# Hutschienenmoped_XL_12V.net
KiCad netlist of a schematic drawn in EAGLE
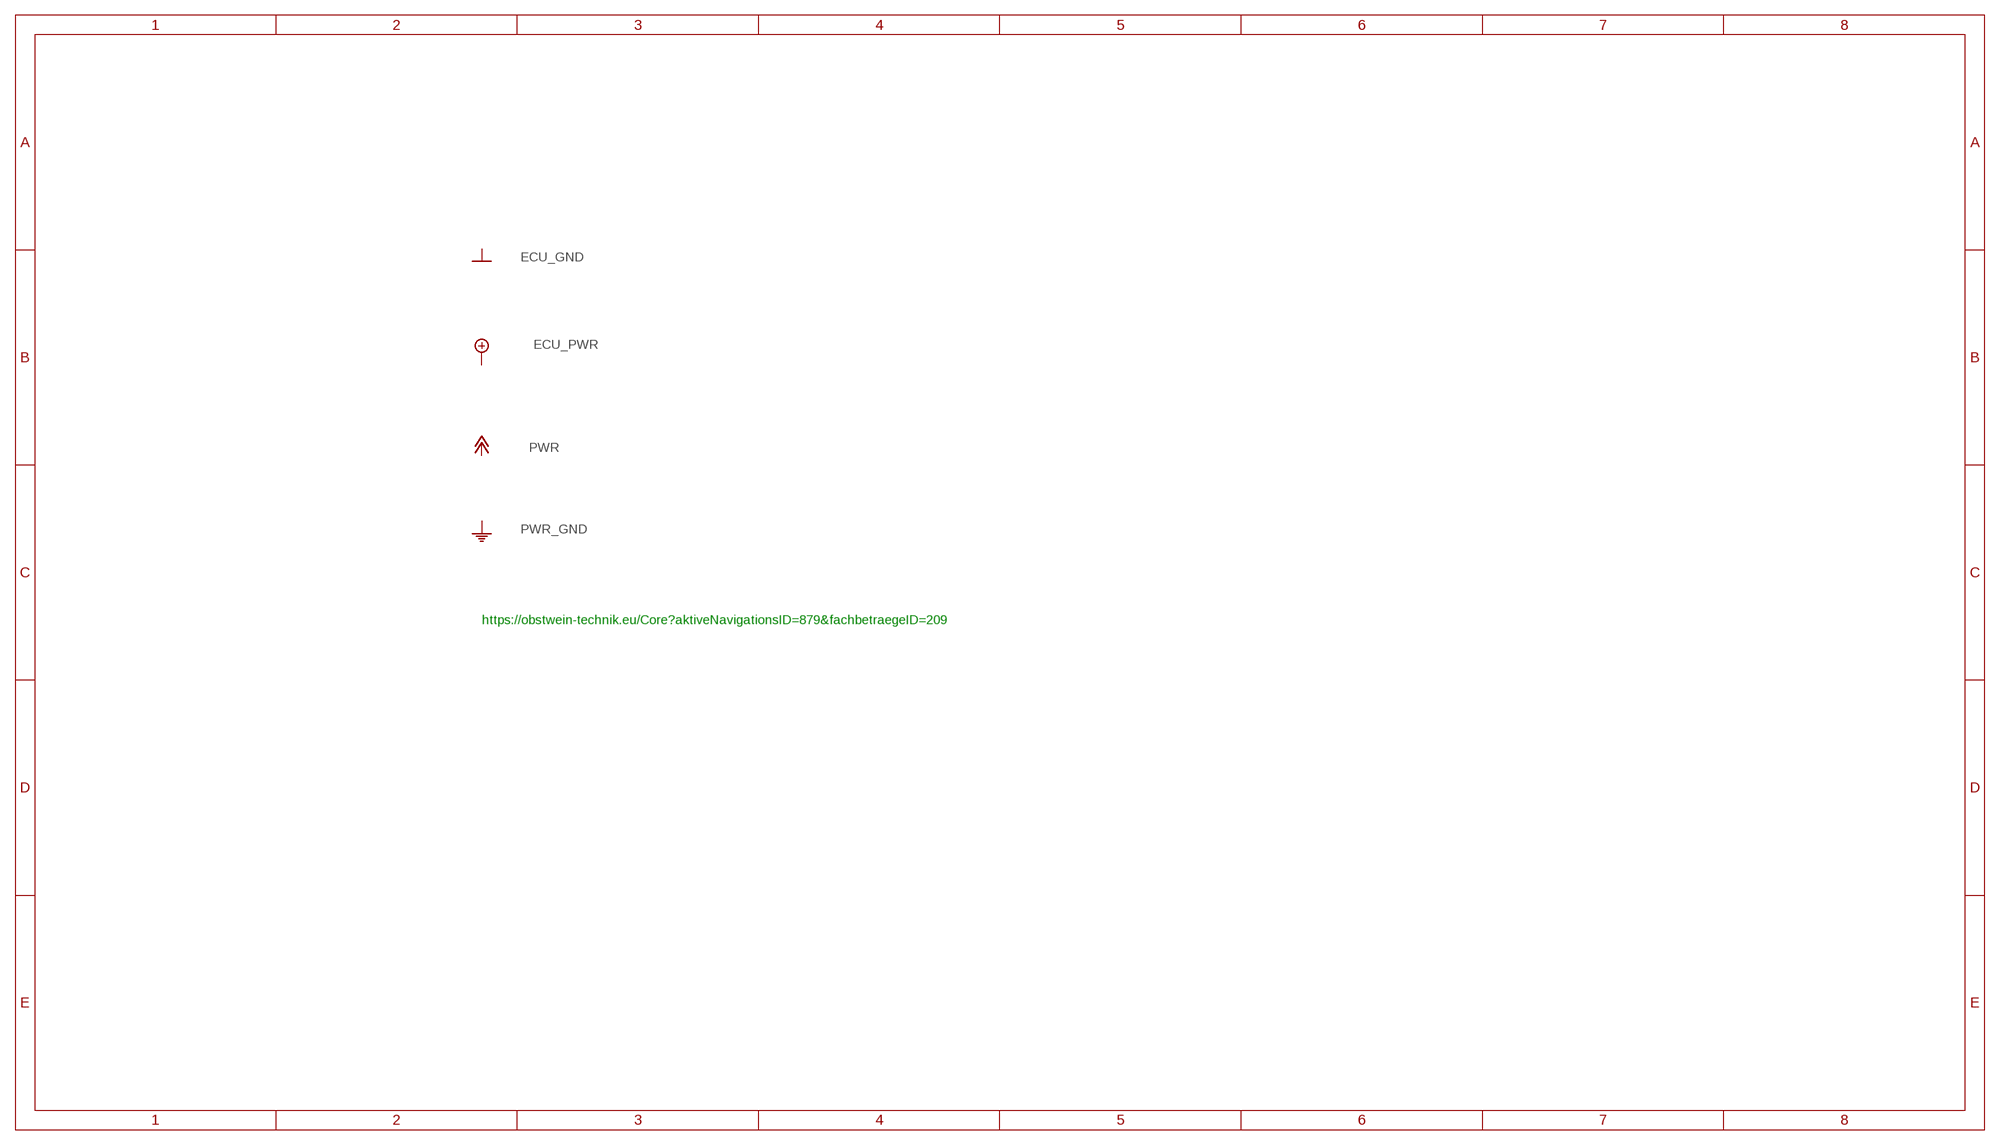
[diagram p0: schematic, sheet 1]
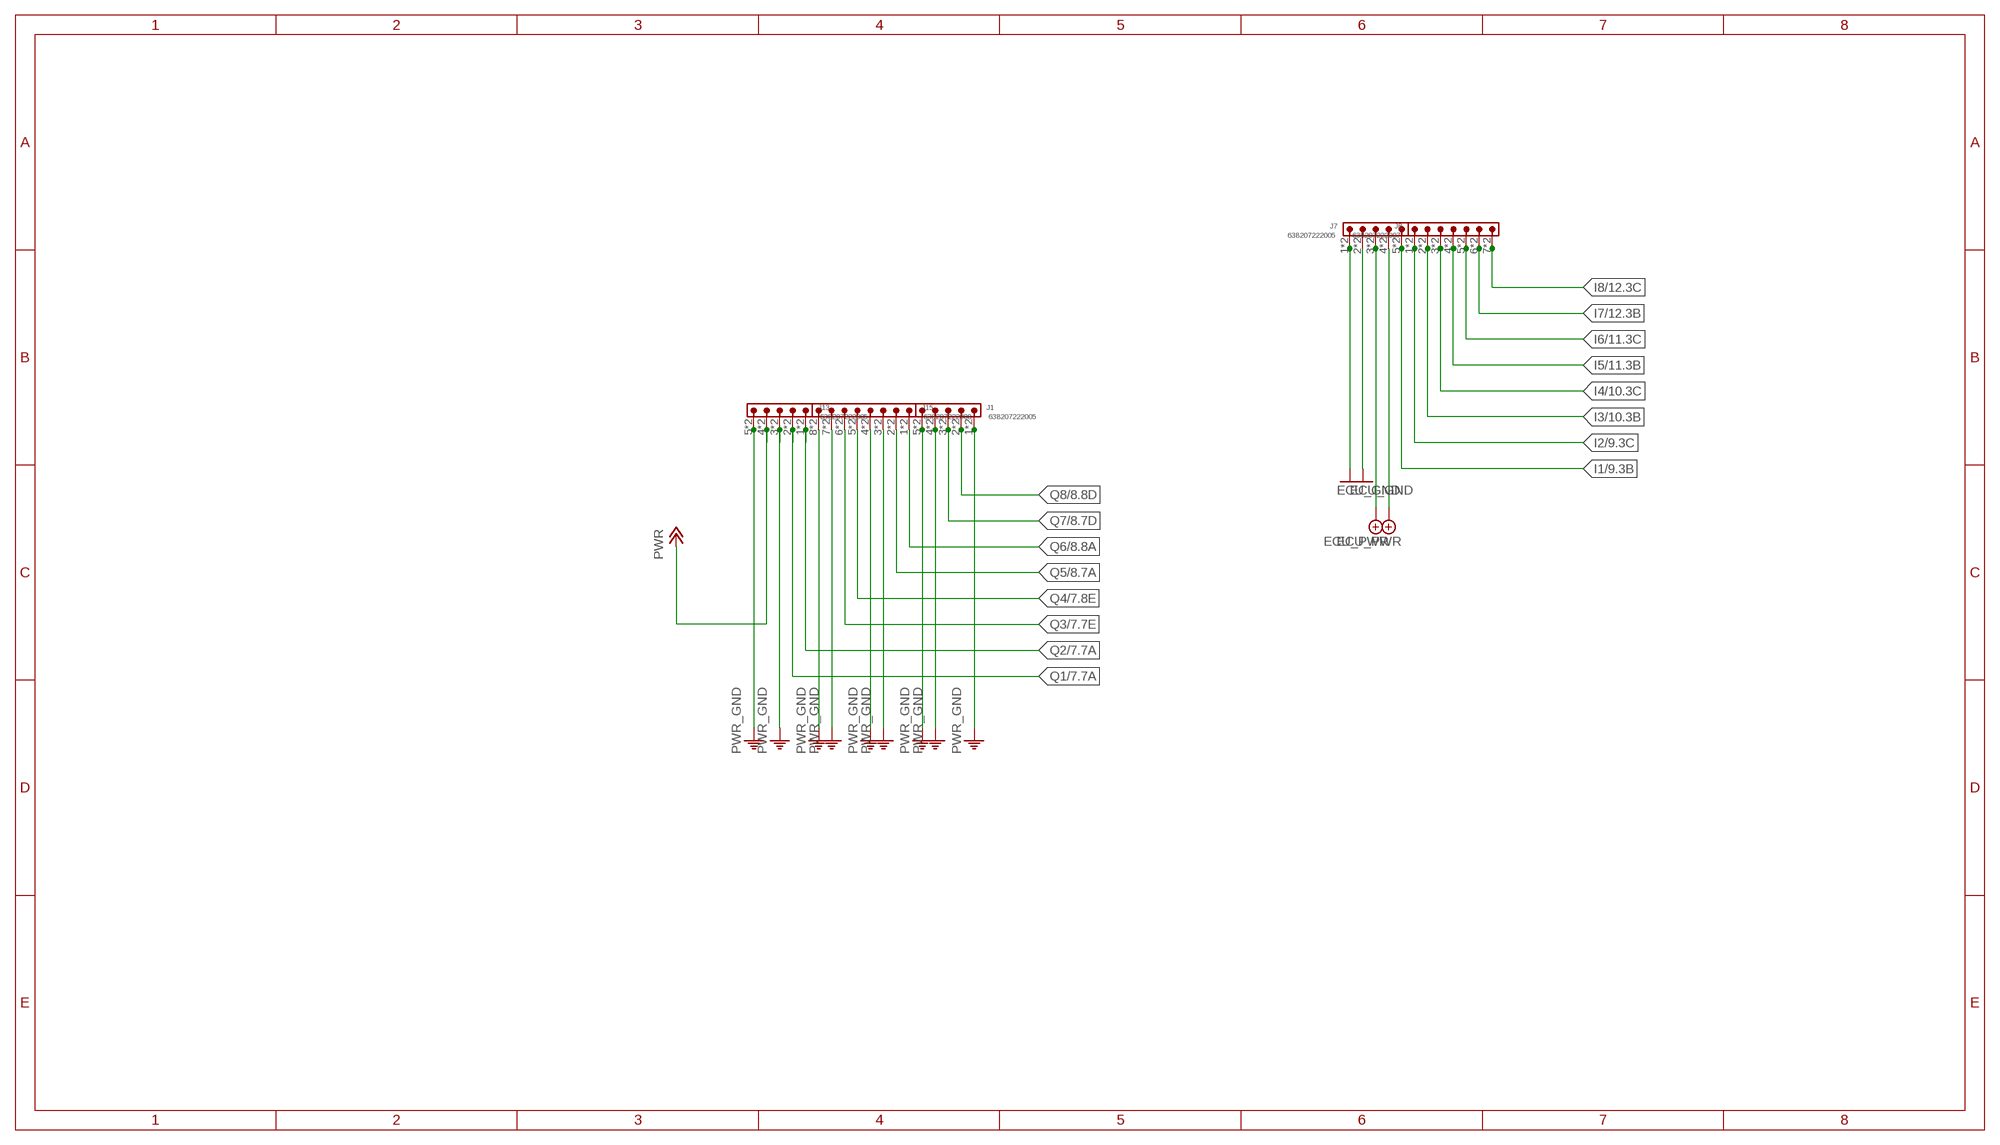
[diagram p1: schematic, sheet 2]
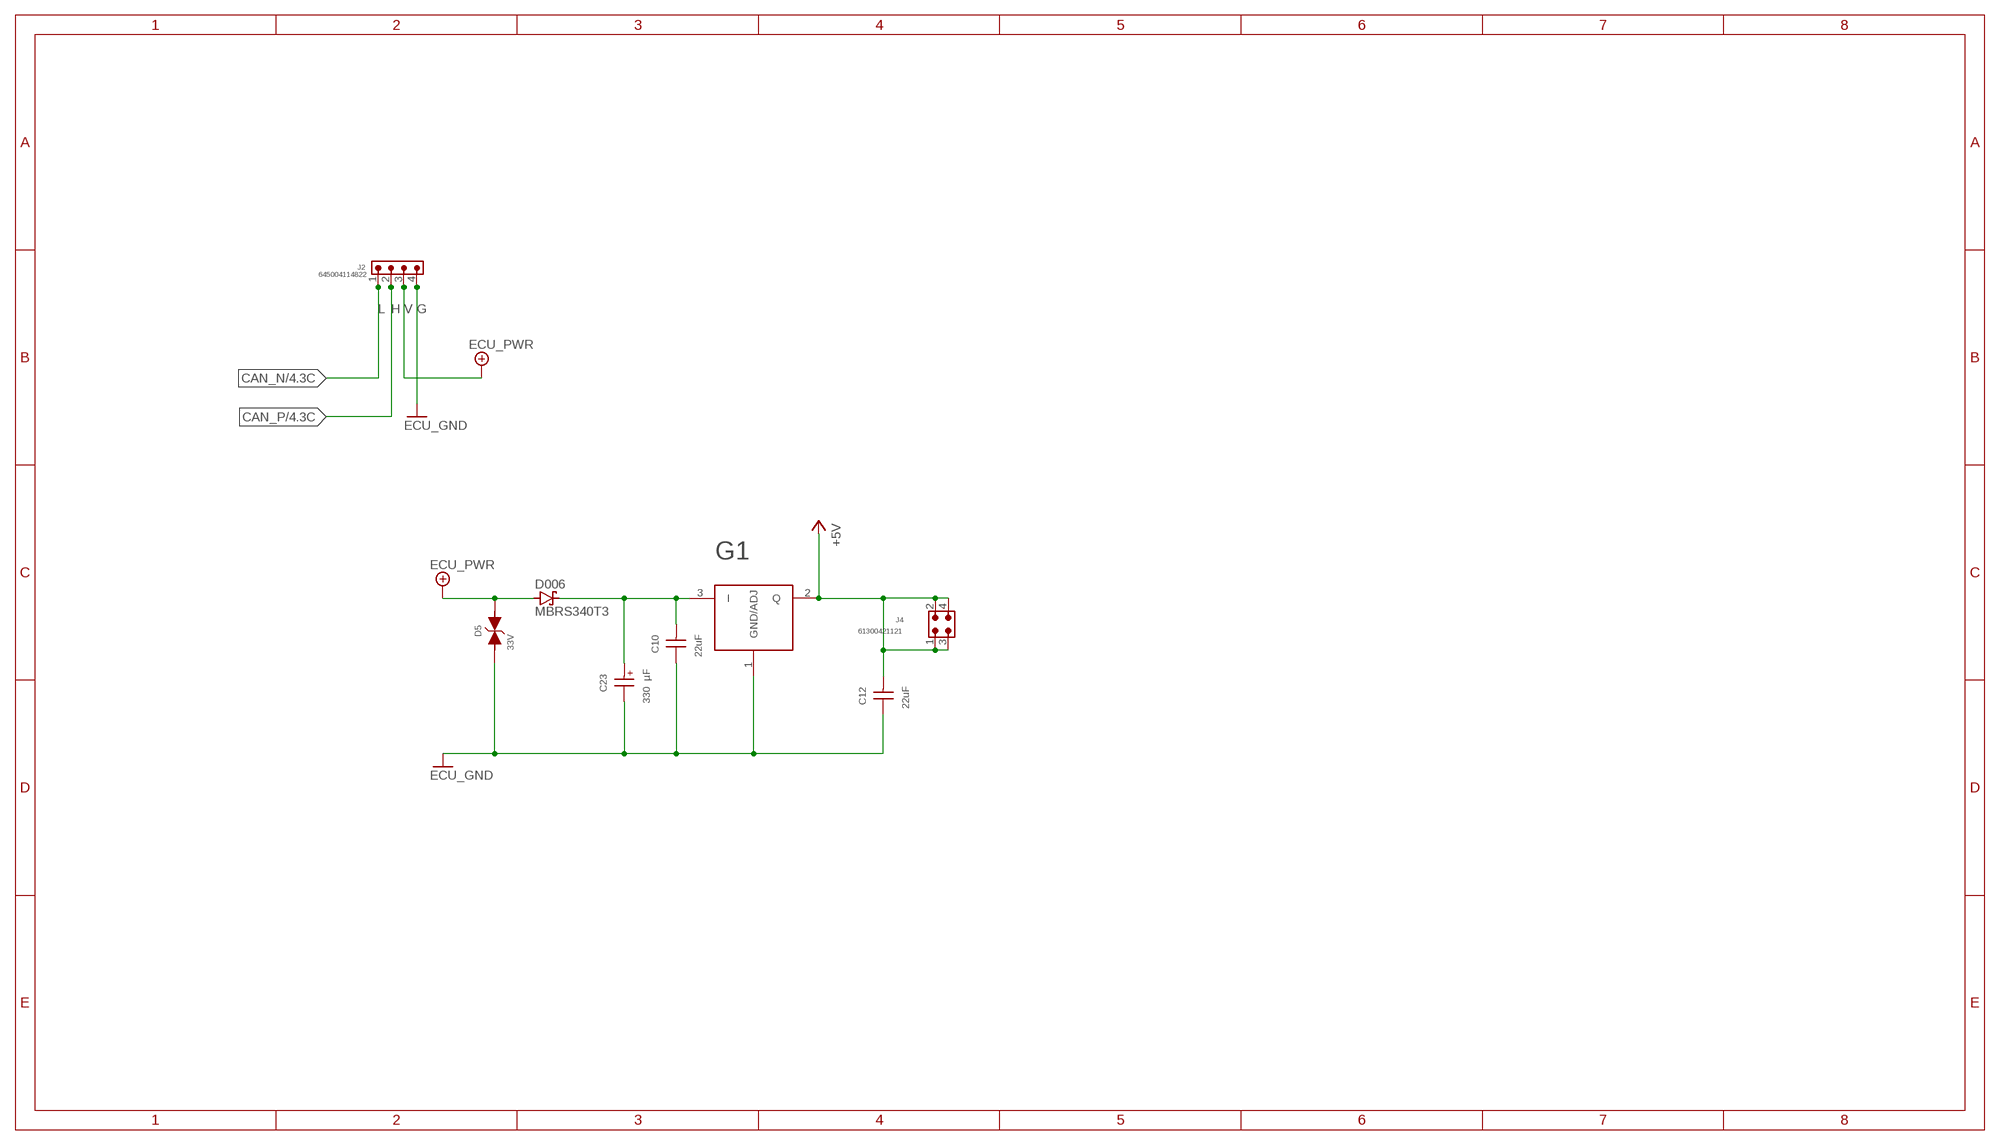
[diagram p2: schematic, sheet 3]
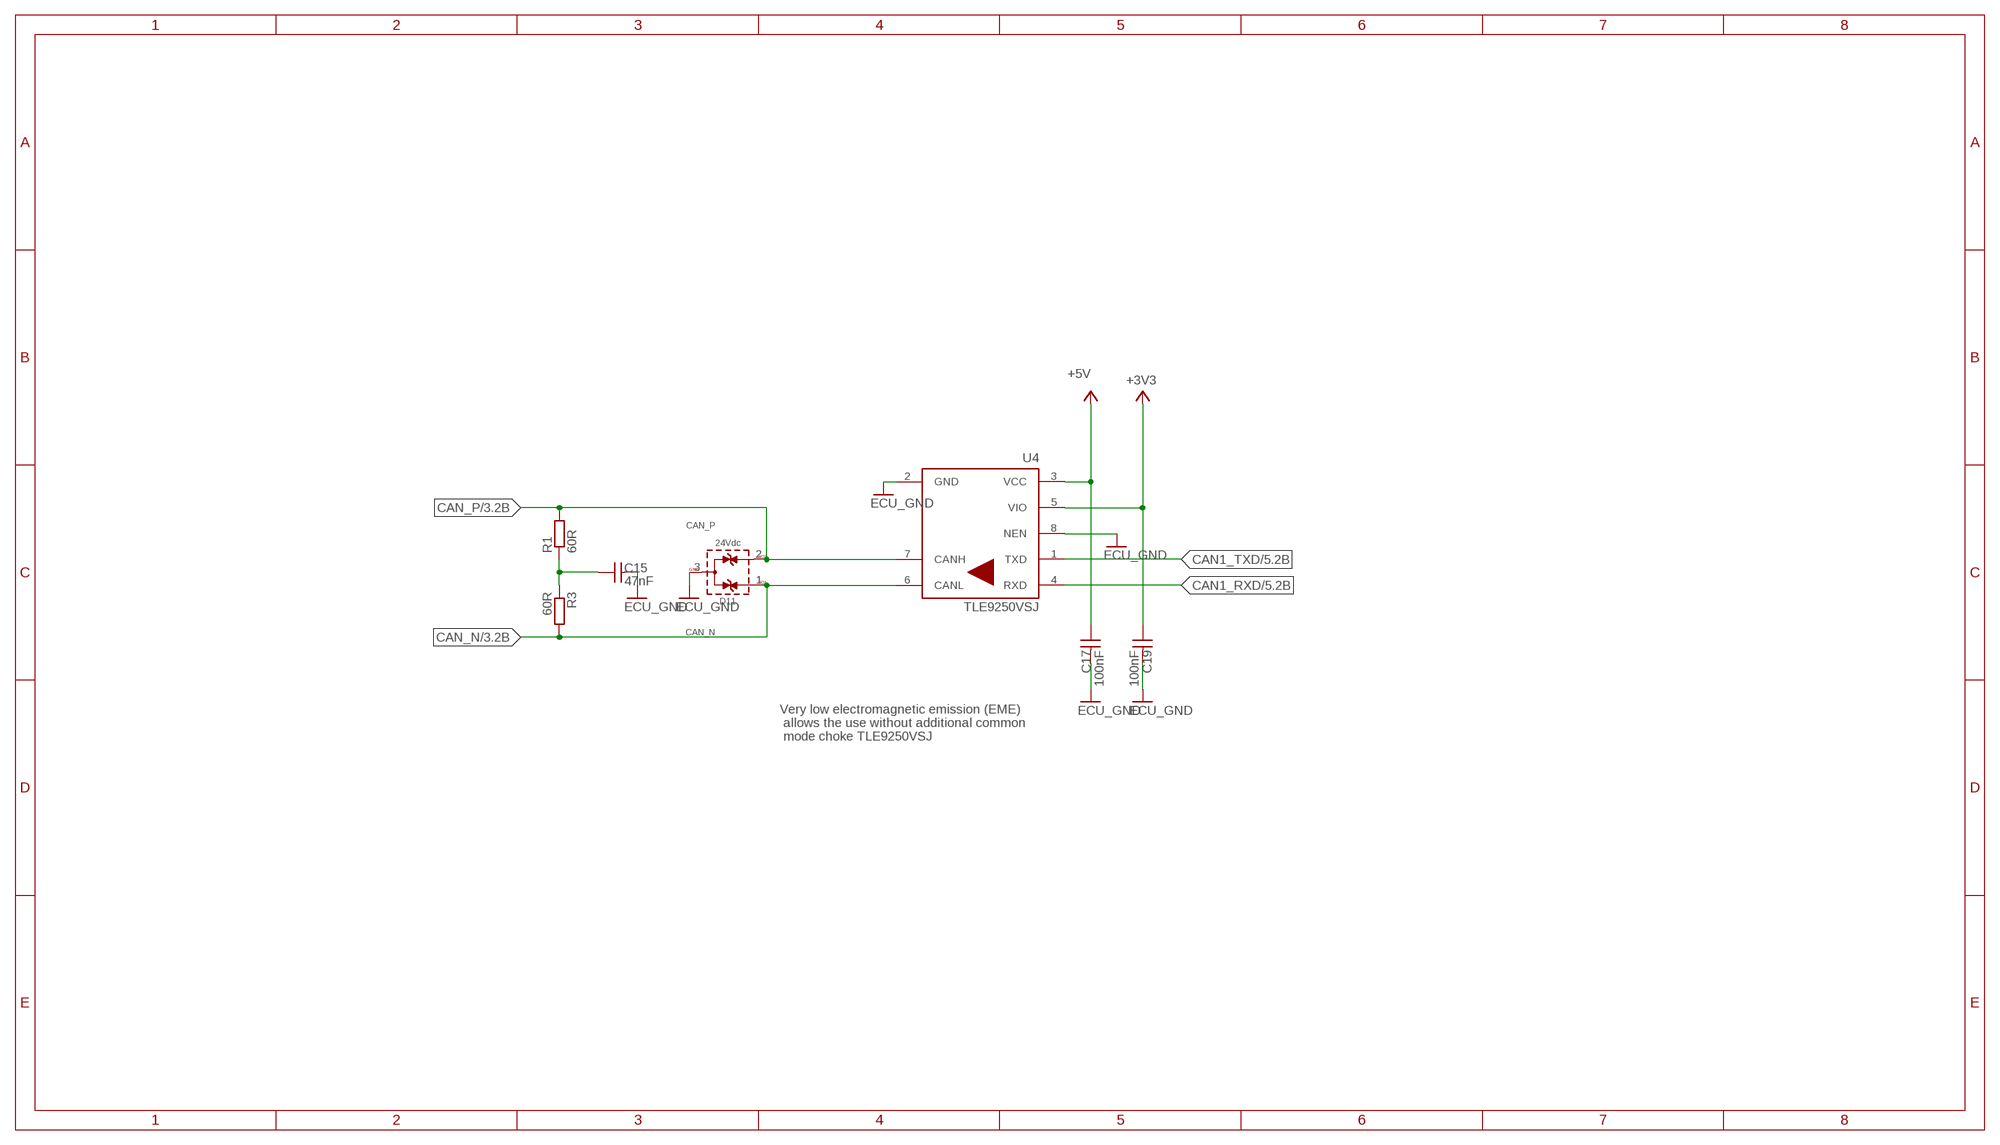
[diagram p3: schematic, sheet 4]
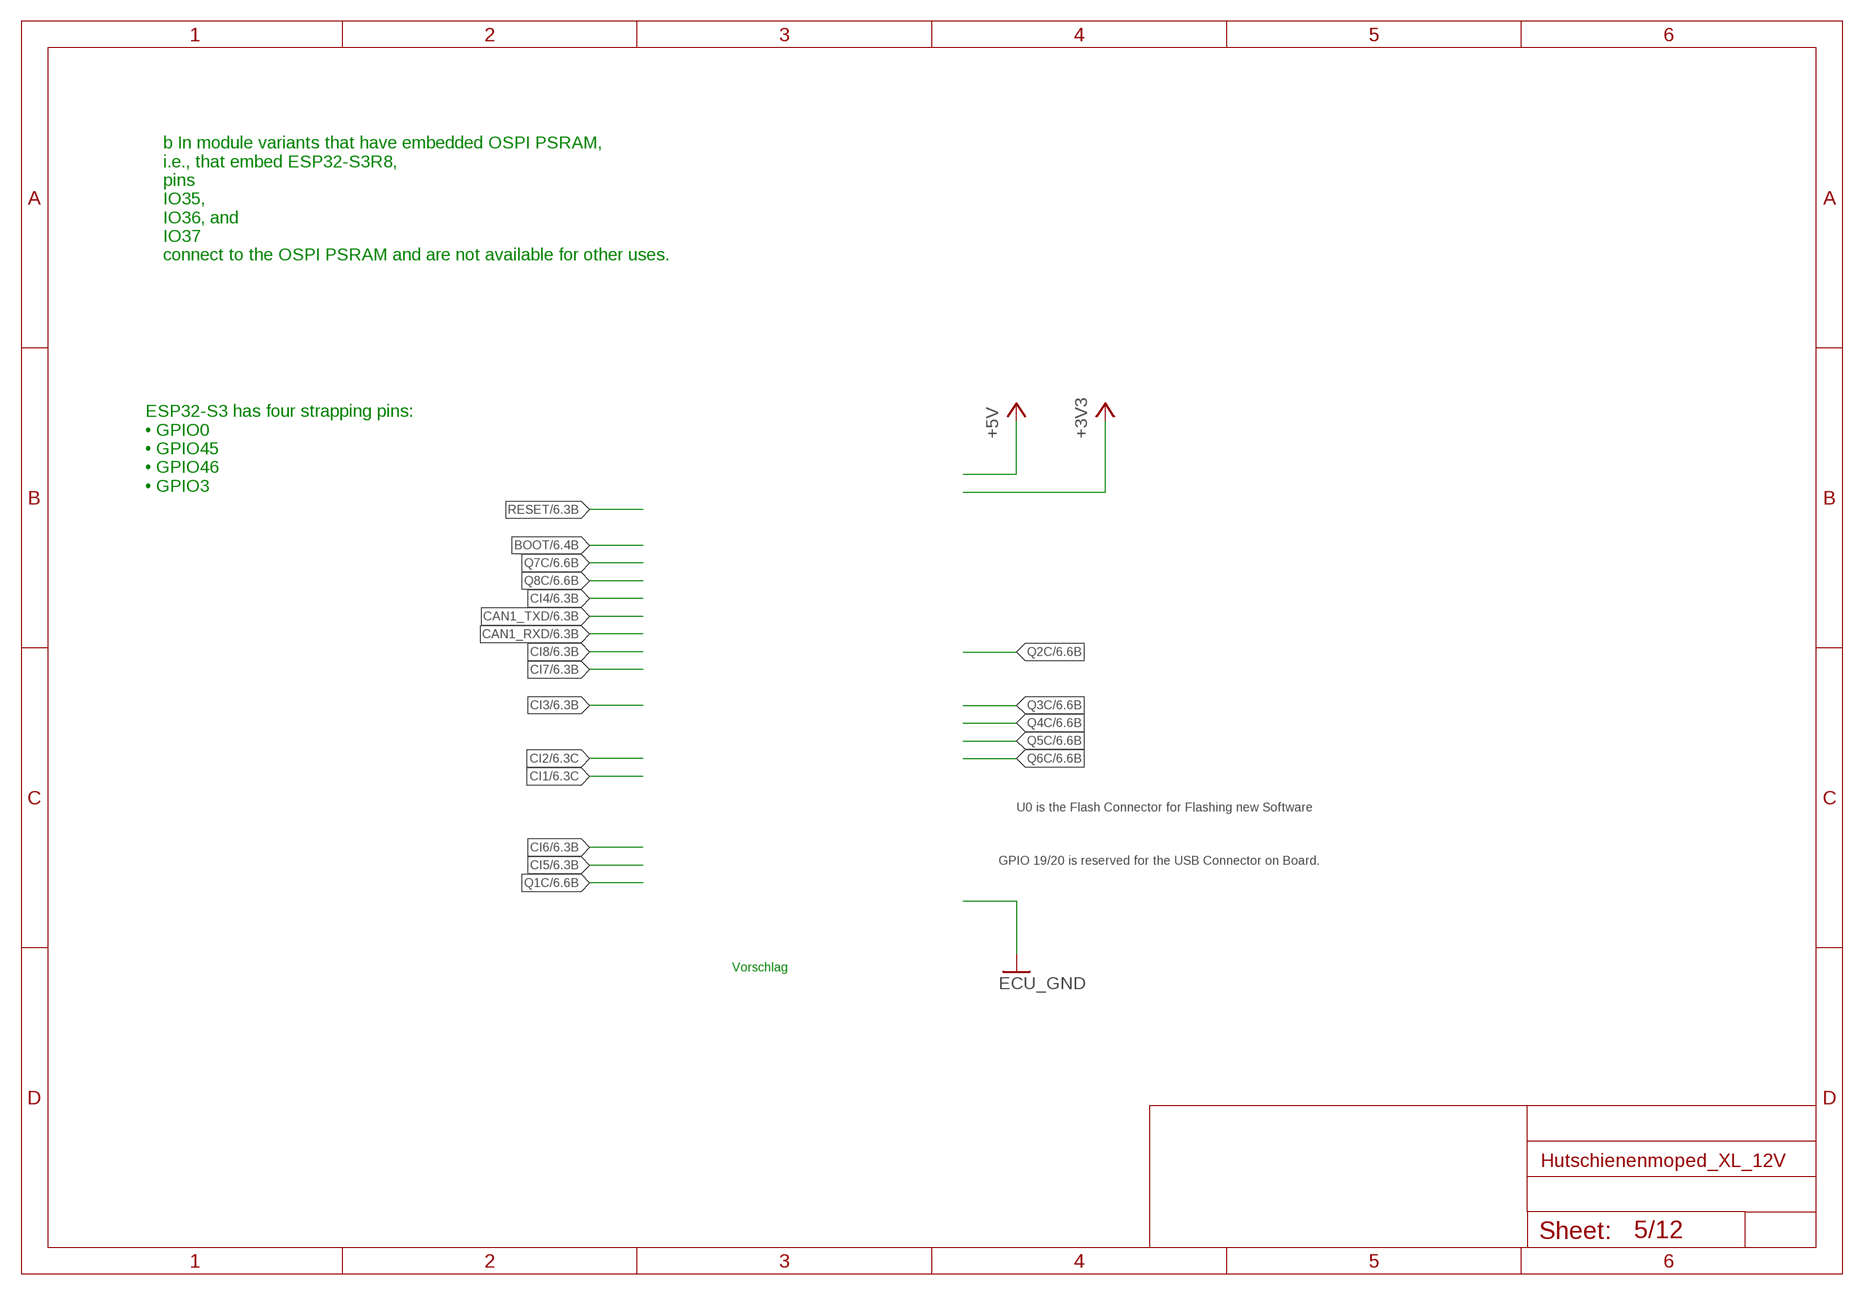
[diagram p4: schematic, sheet 5]
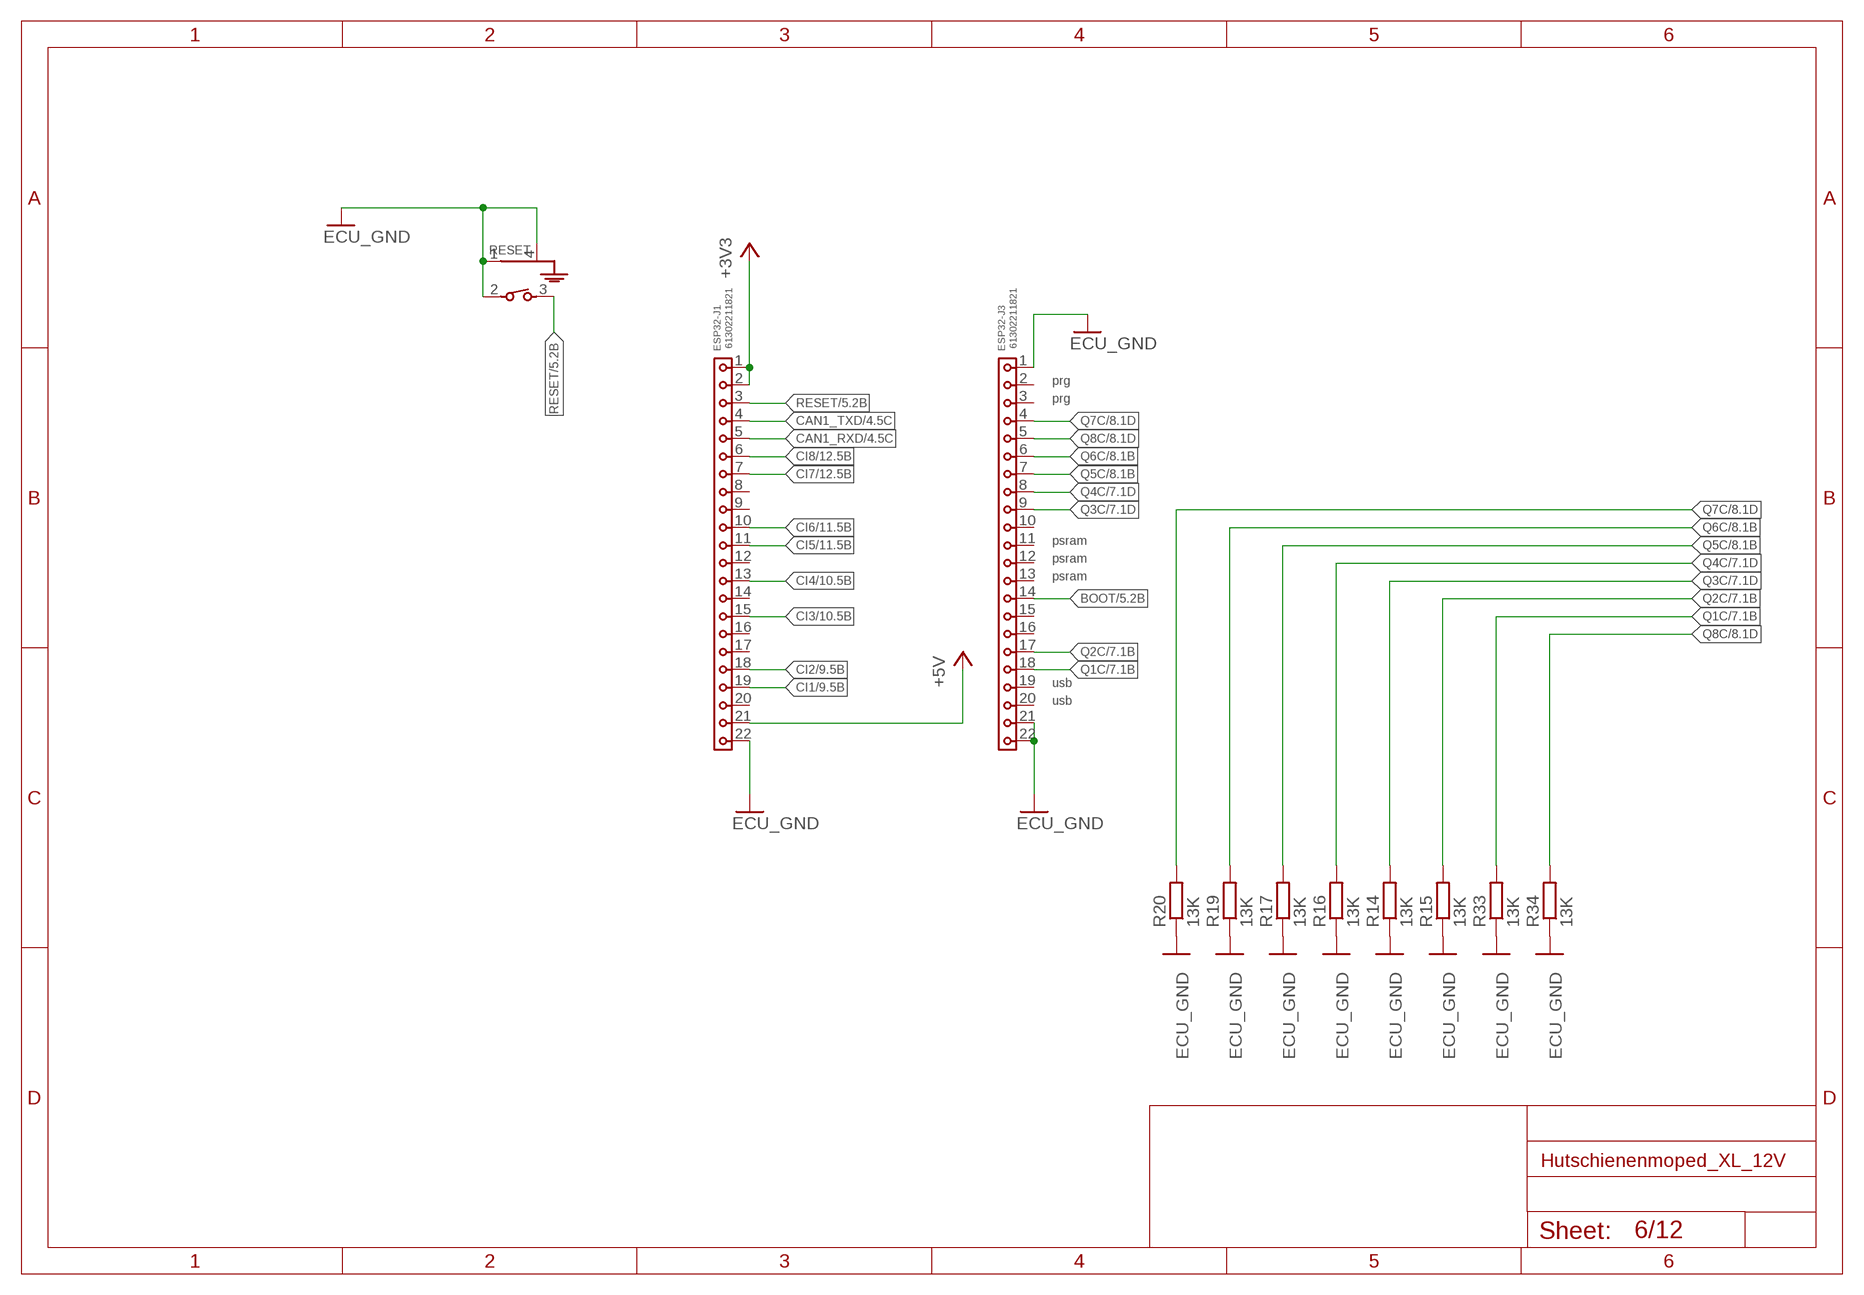
[diagram p5: schematic, sheet 6]
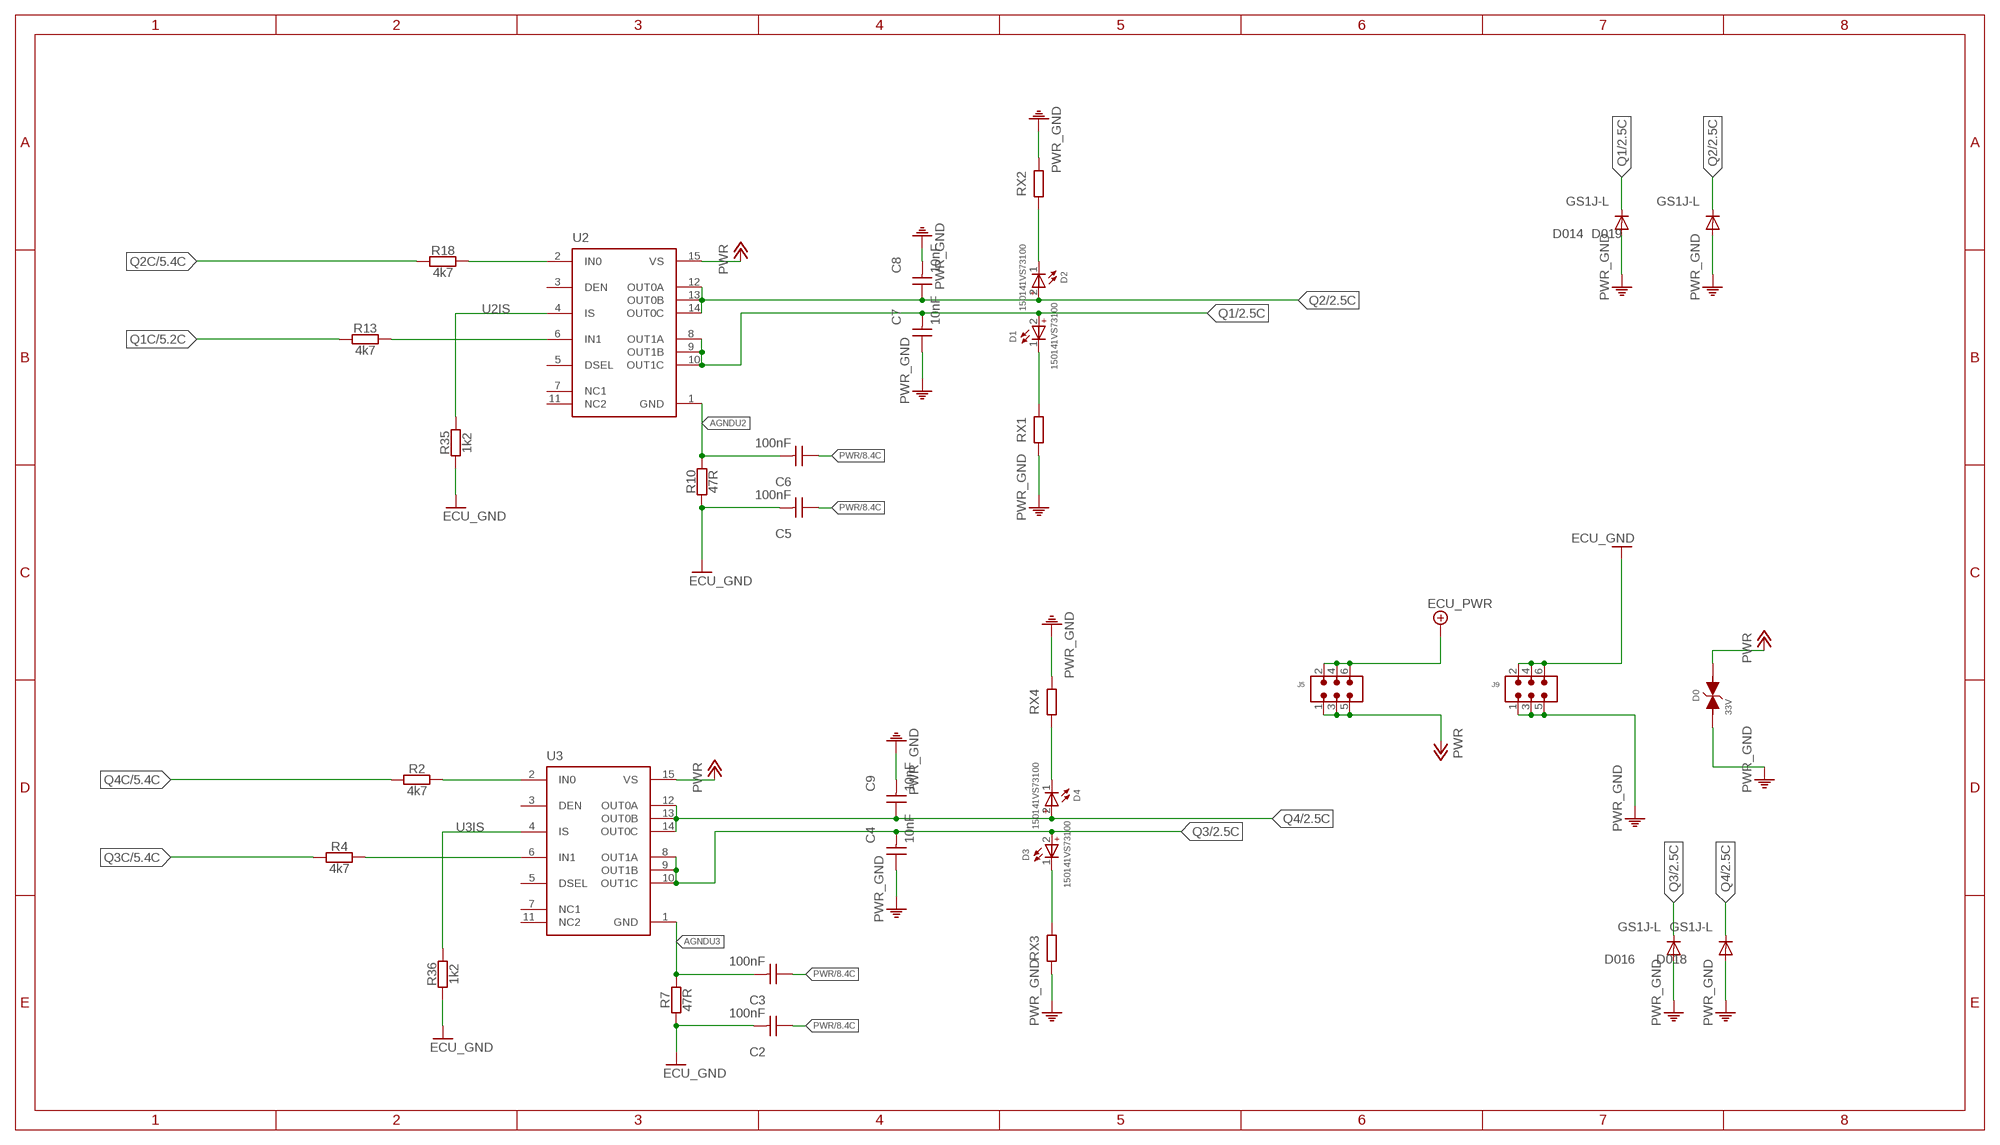
[diagram p6: schematic, sheet 7]
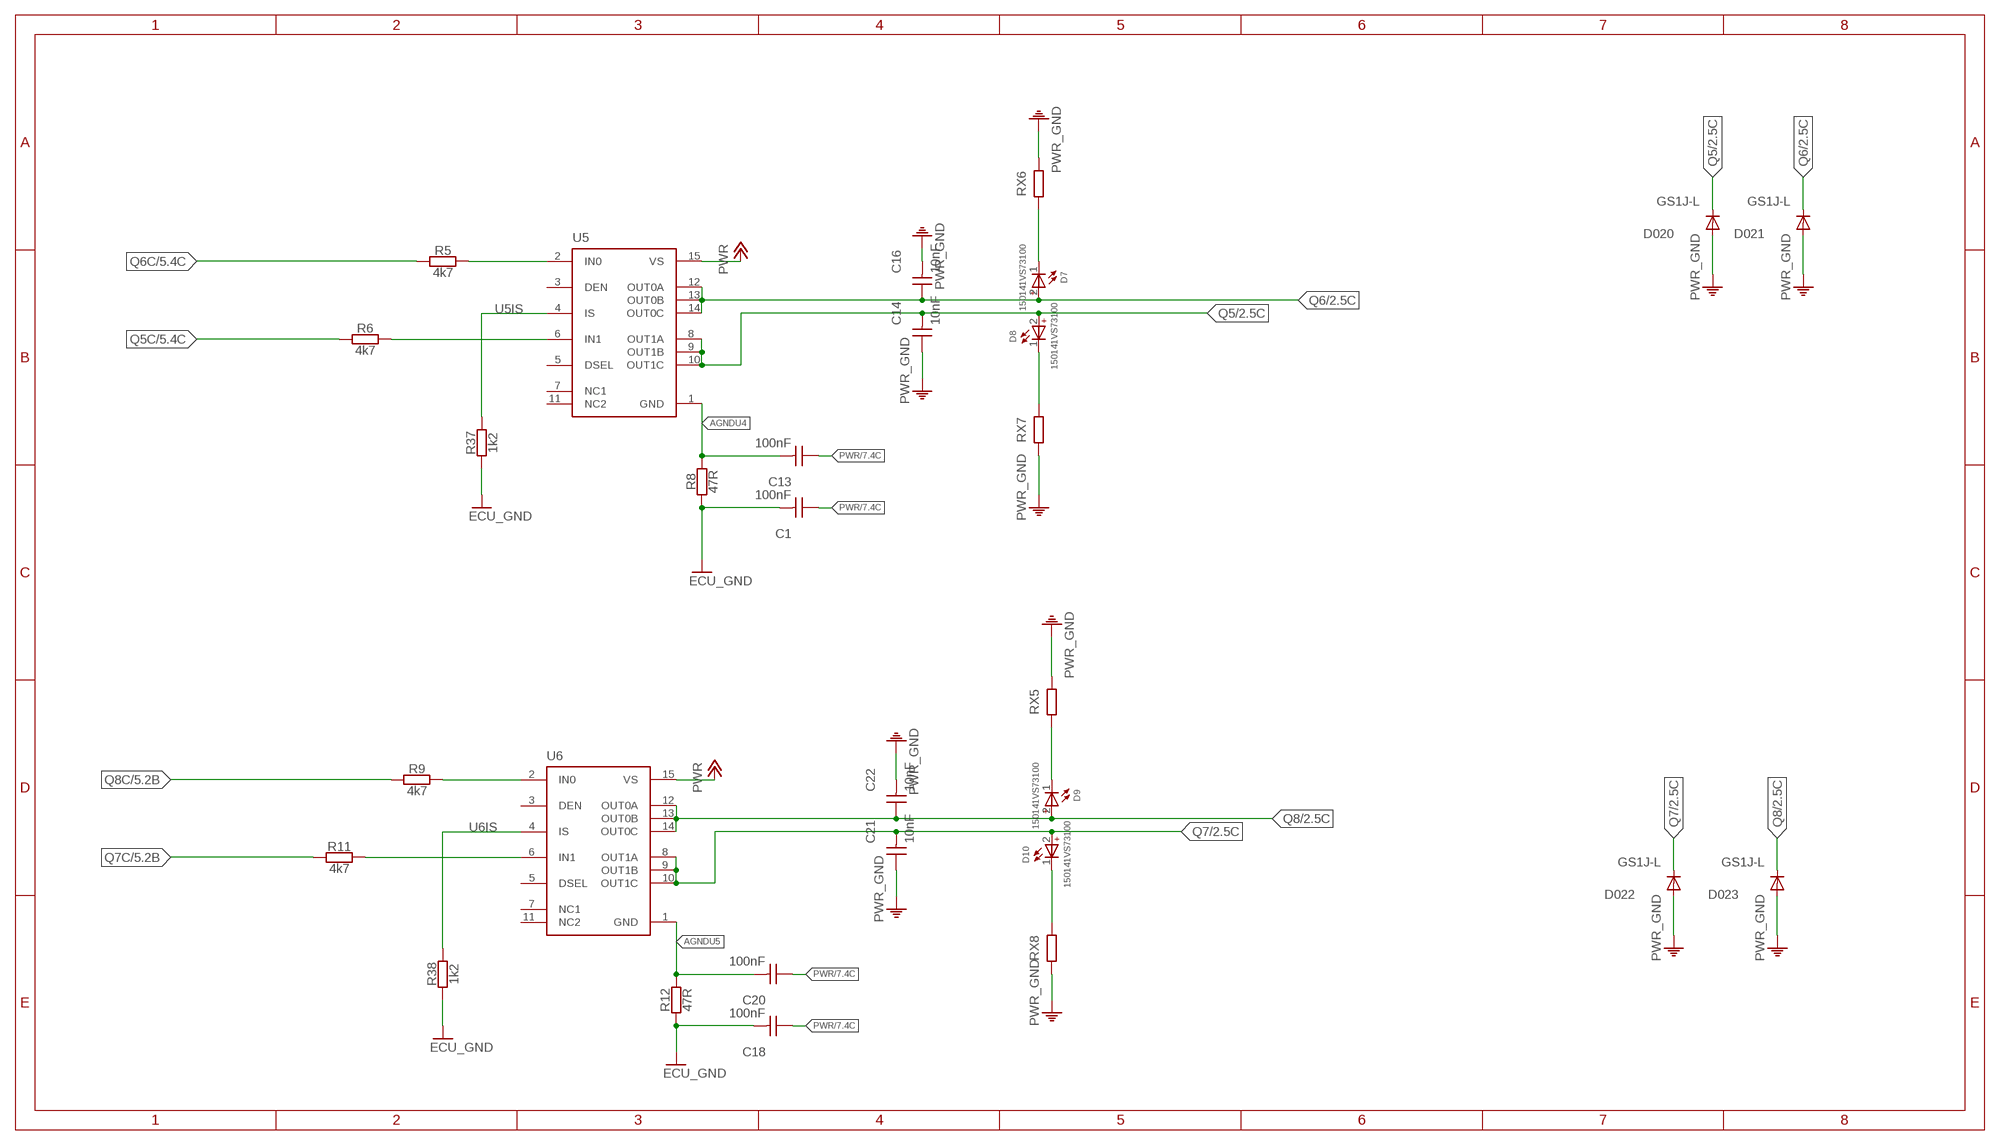
[diagram p7: schematic, sheet 8]
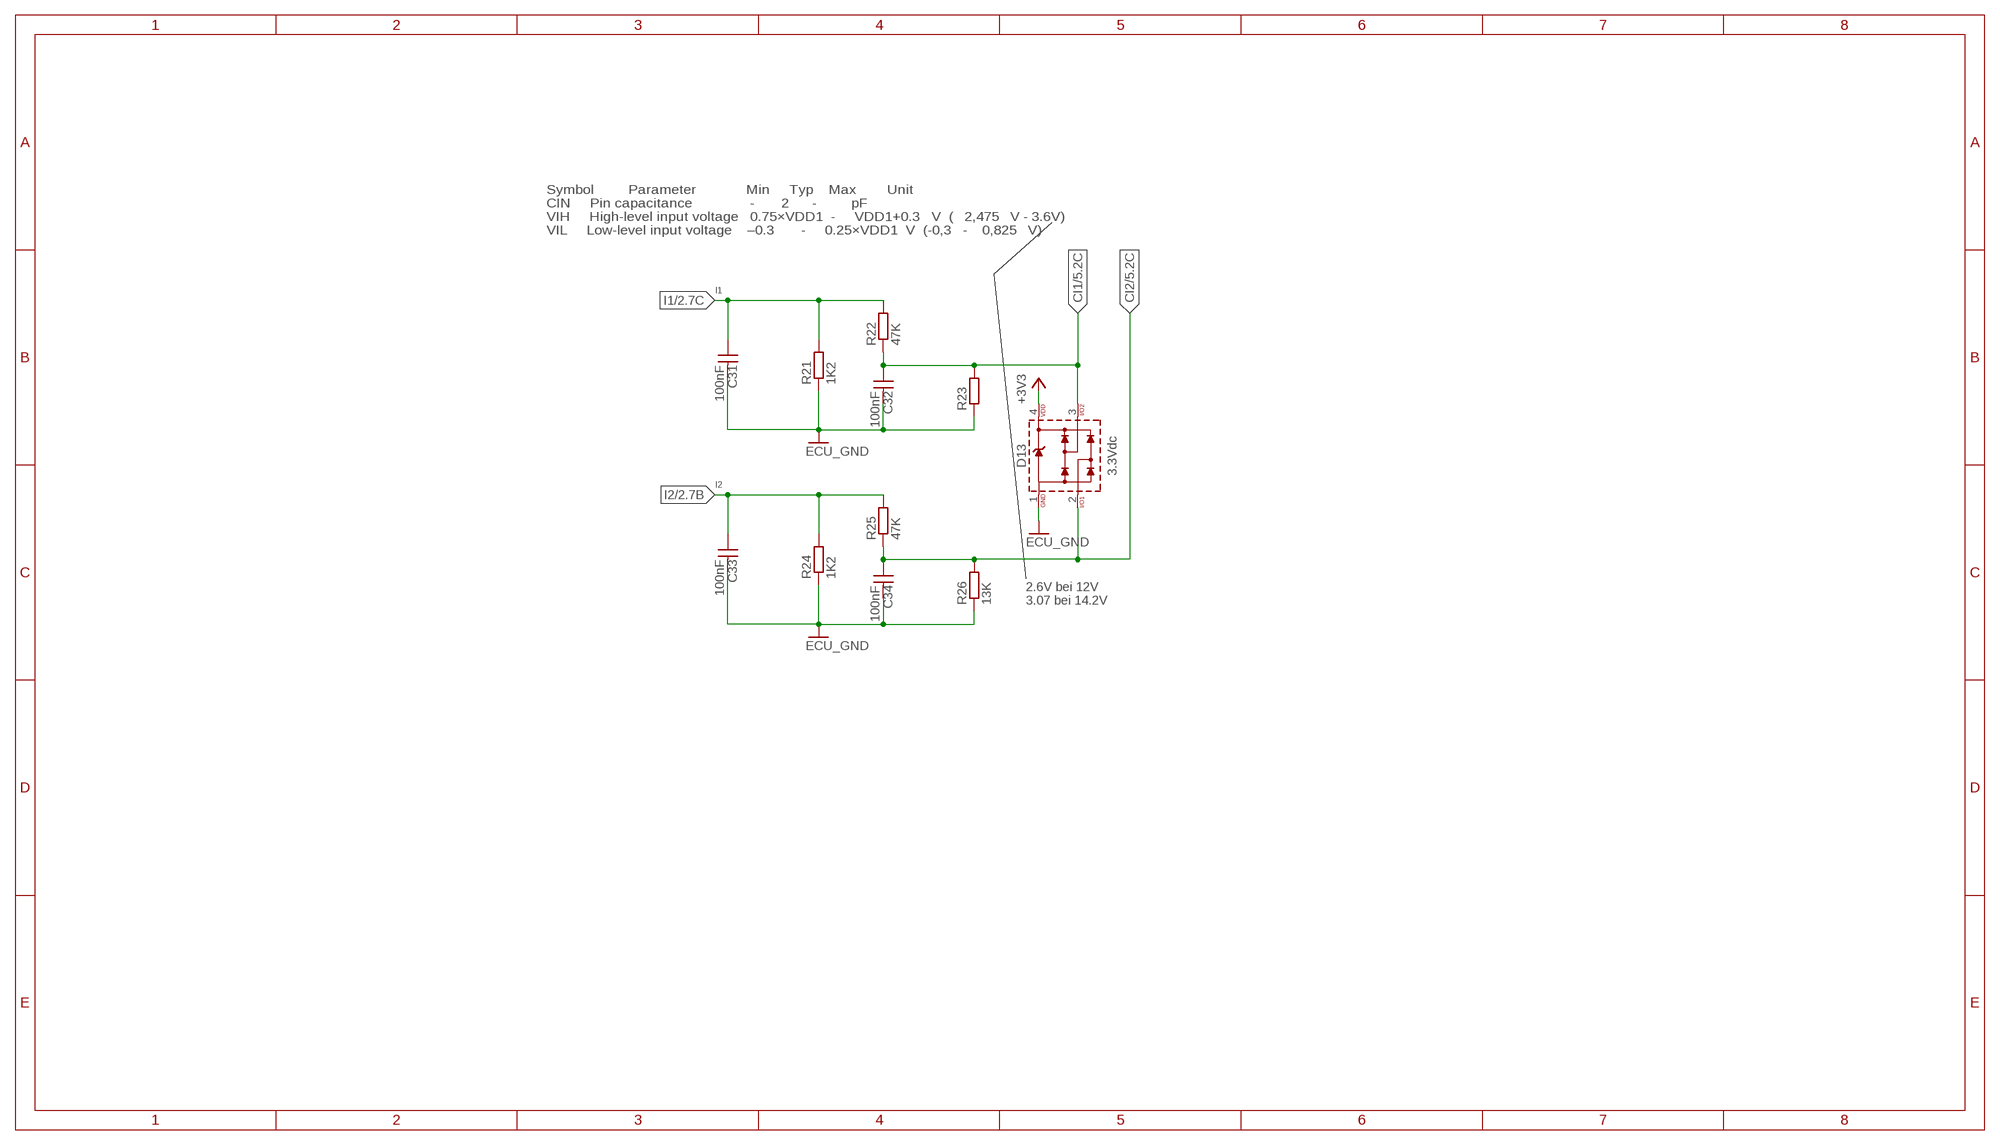
[diagram p8: schematic, sheet 9]
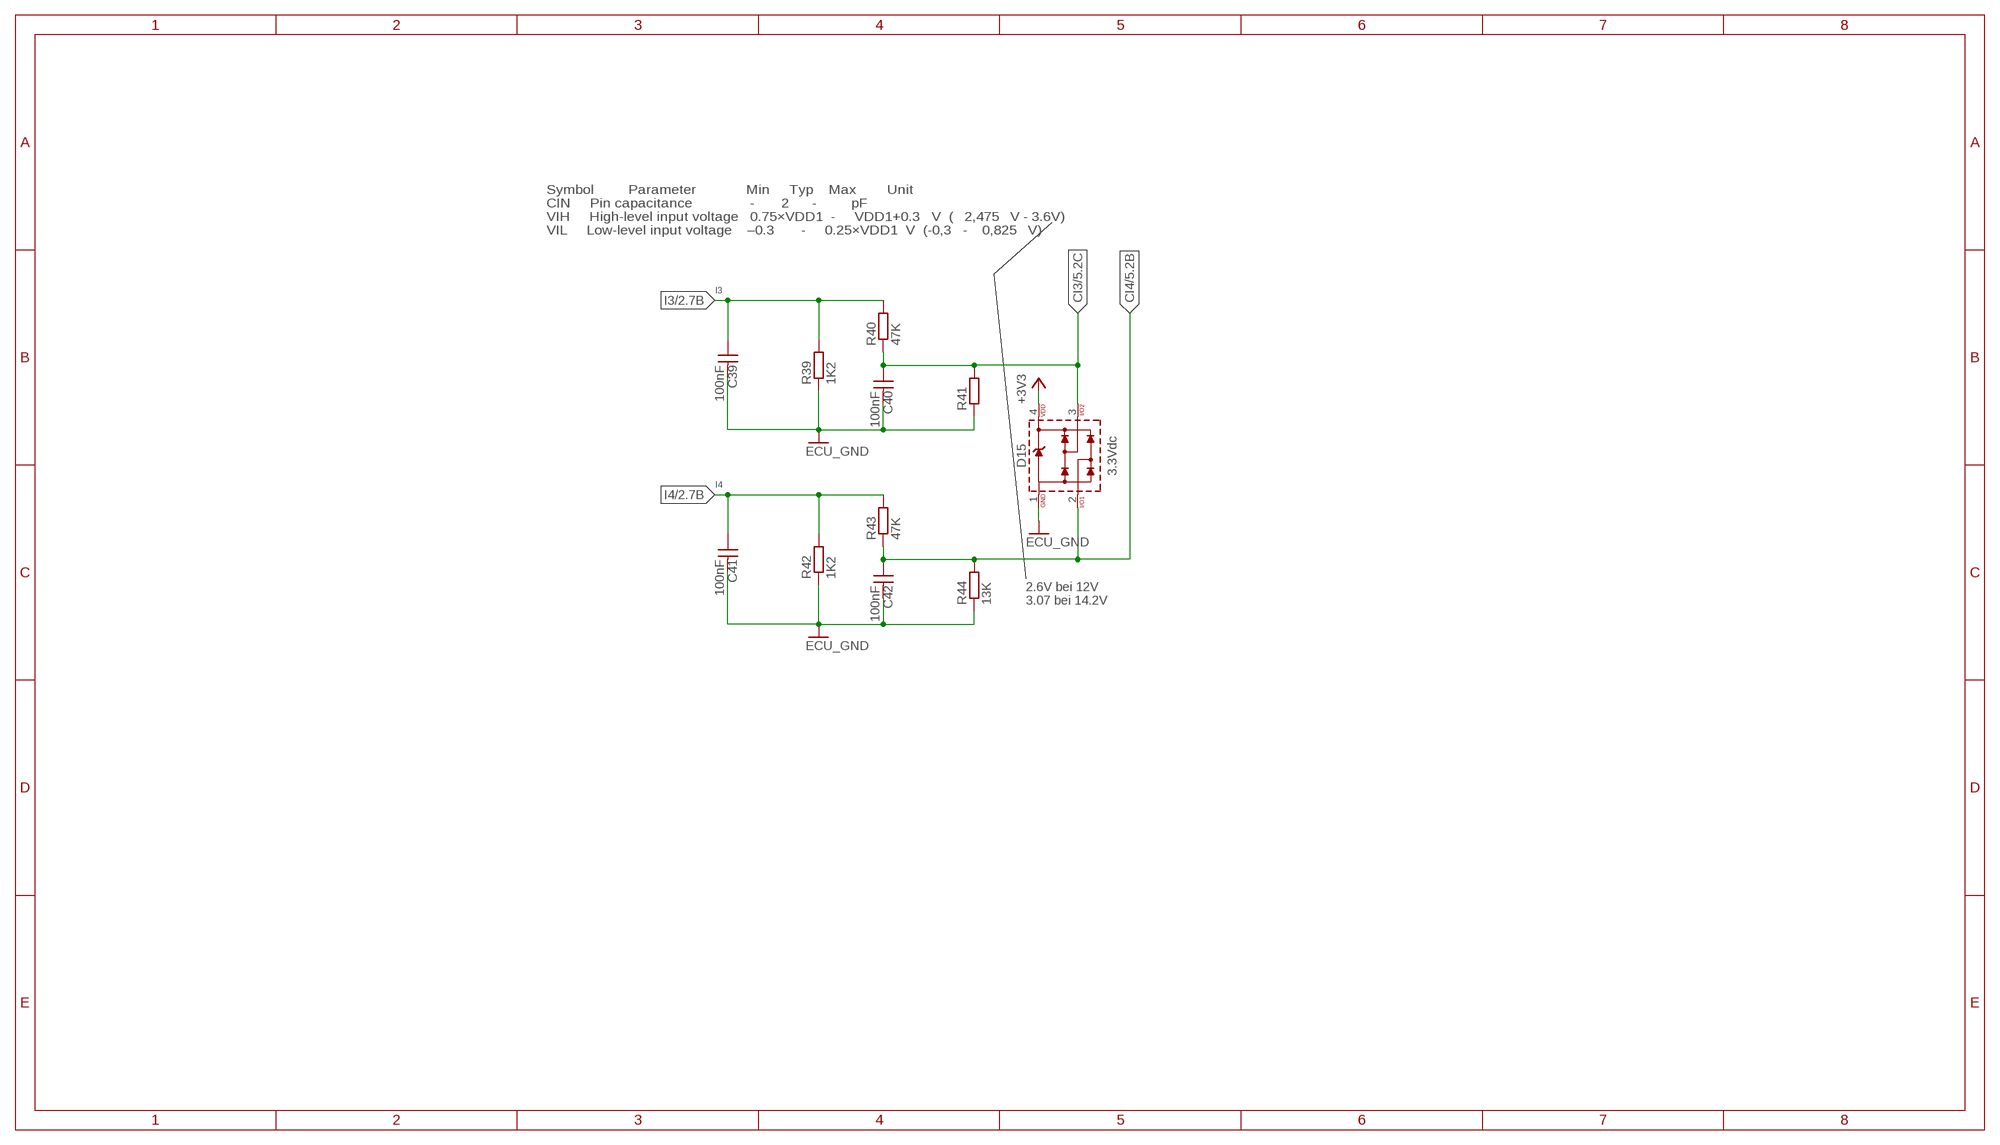
[diagram p9: schematic, sheet 10]
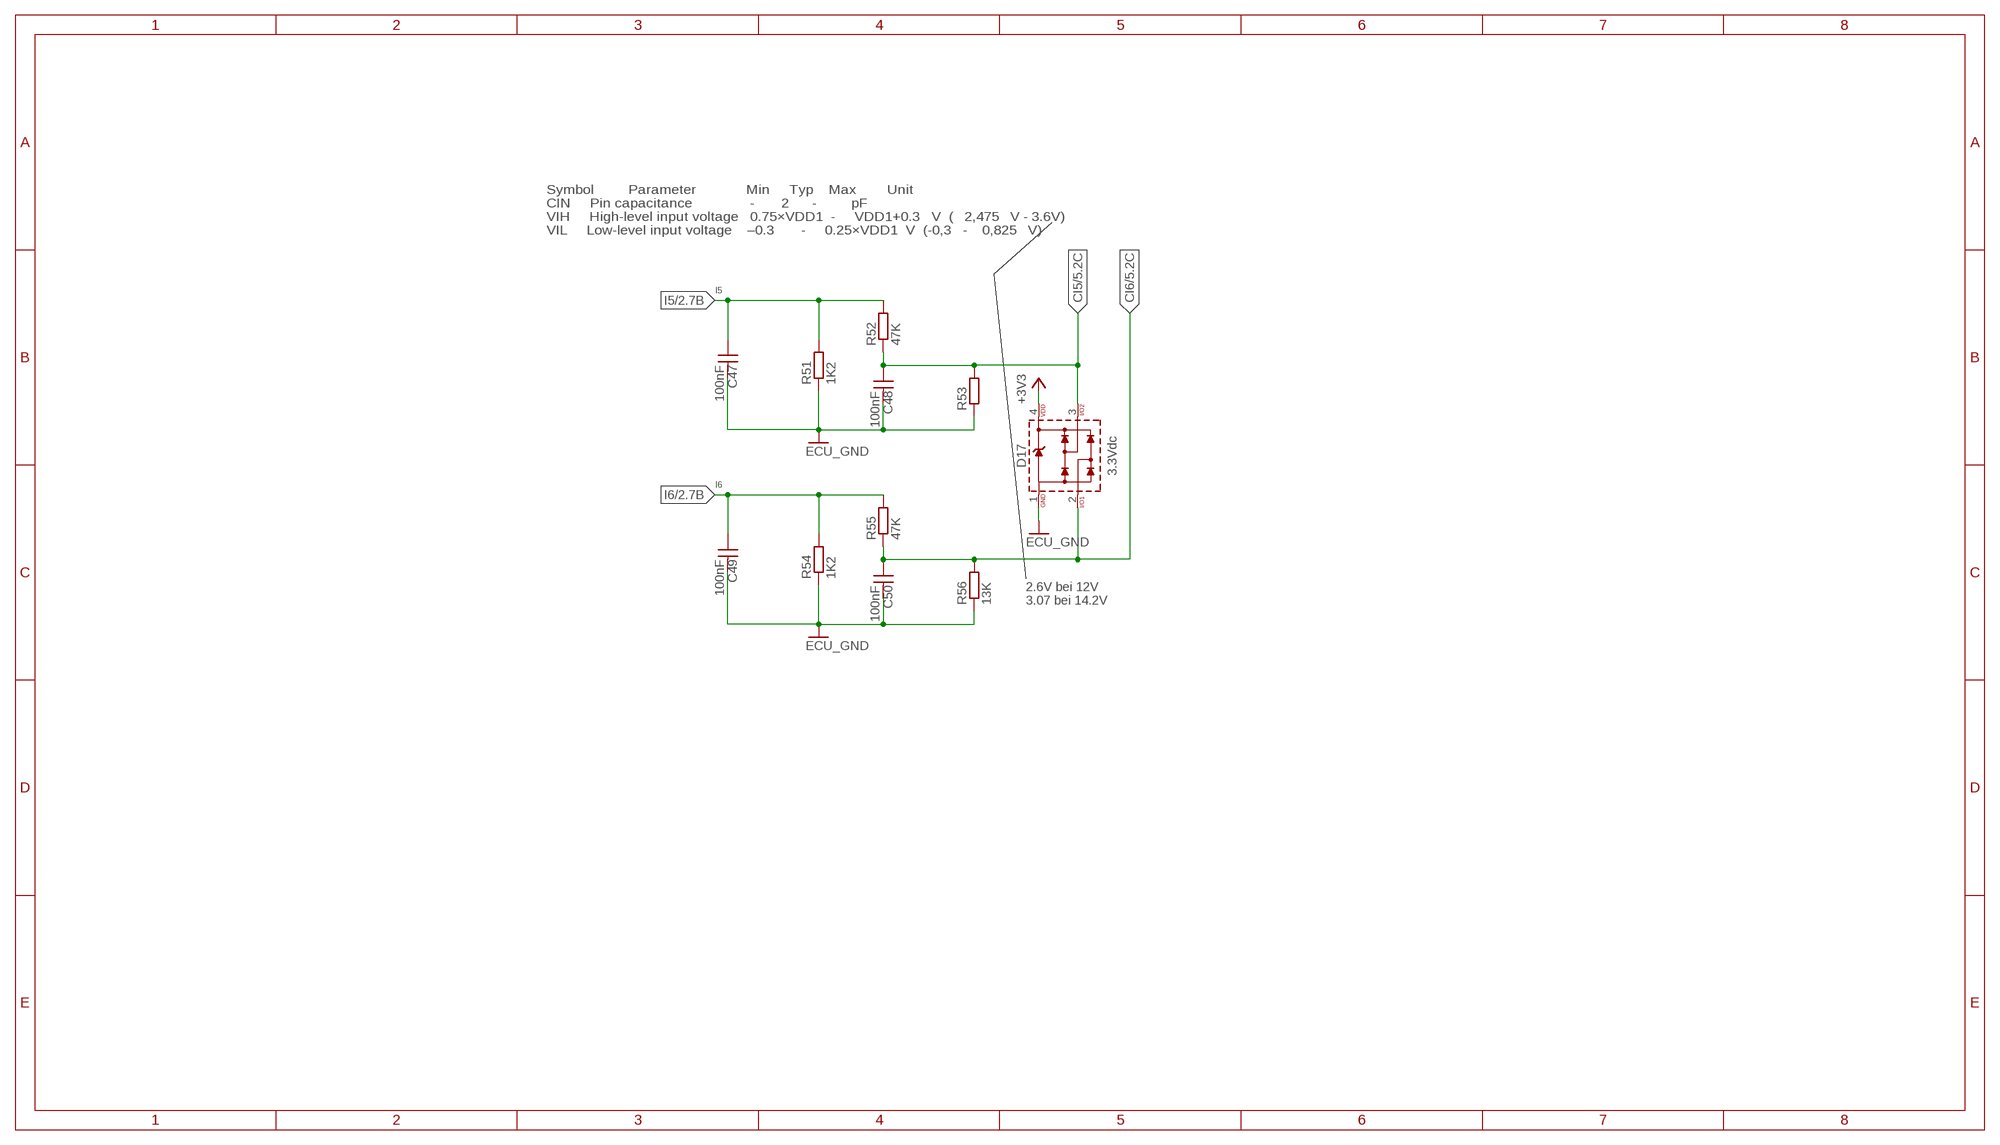
[diagram p10: schematic, sheet 11]
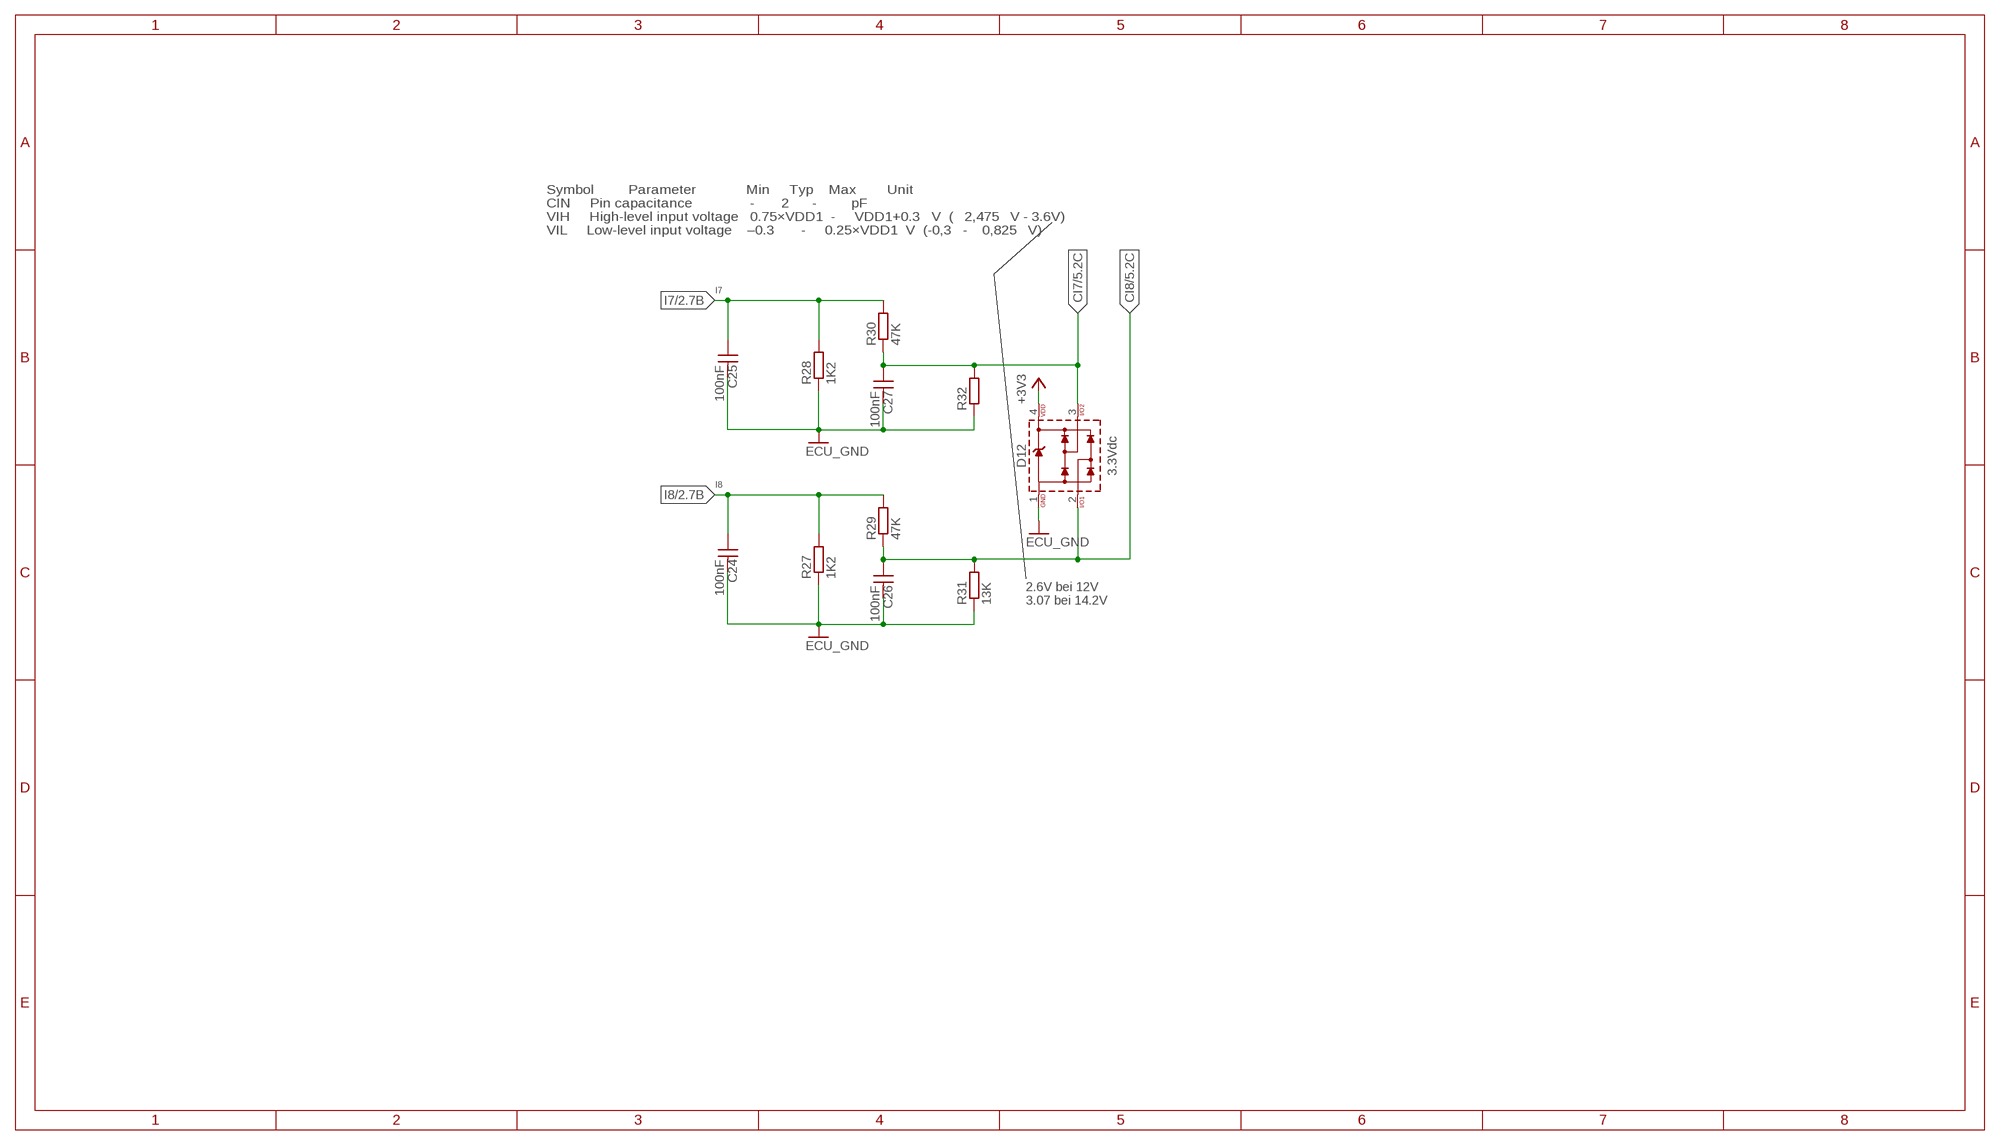
[diagram p11: schematic, sheet 12]

(export (version "E")
  (design (tool "Eeschema 10.0.6"))
  (components
    (comp (ref "J1")
      (value "638207222005")
      (footprint "eagle-import:638207222005")
      (libsource (lib "eagle-import") (part "638207222005"))
    )
    (comp (ref "J7")
      (value "638207222005")
      (footprint "eagle-import:638207222005")
      (libsource (lib "eagle-import") (part "638207222005"))
    )
    (comp (ref "J8")
      (value "638207222007")
      (footprint "eagle-import:638207222007")
      (libsource (lib "eagle-import") (part "638207222007"))
    )
    (comp (ref "J13")
      (value "638207222005")
      (footprint "eagle-import:638207222005")
      (libsource (lib "eagle-import") (part "638207222005"))
    )
    (comp (ref "J15")
      (value "638207222008")
      (footprint "eagle-import:638207222008")
      (libsource (lib "eagle-import") (part "638207222008"))
    )
    (comp (ref "C39")
      (value "100nF")
      (footprint "eagle-import:WCAP-CSGP_1206_H0.8")
      (libsource (lib "eagle-import") (part "WCAP-CSGP_1206_H0.8_50V(DC)_885012208087"))
    )
    (comp (ref "C40")
      (value "100nF")
      (footprint "eagle-import:WCAP-CSGP_1206_H0.8")
      (libsource (lib "eagle-import") (part "WCAP-CSGP_1206_H0.8_50V(DC)_885012208087"))
    )
    (comp (ref "C41")
      (value "100nF")
      (footprint "eagle-import:WCAP-CSGP_1206_H0.8")
      (libsource (lib "eagle-import") (part "WCAP-CSGP_1206_H0.8_50V(DC)_885012208087"))
    )
    (comp (ref "C42")
      (value "100nF")
      (footprint "eagle-import:WCAP-CSGP_1206_H0.8")
      (libsource (lib "eagle-import") (part "WCAP-CSGP_1206_H0.8_50V(DC)_885012208087"))
    )
    (comp (ref "D15")
      (value "3.3Vdc")
      (footprint "eagle-import:WE-TVS_SOT143-4L")
      (libsource (lib "eagle-import") (part "WE-TVS-HS_SOT143-4L_8240136"))
    )
    (comp (ref "R39")
      (value "1K2")
      (footprint "eagle-import:R1206")
      (libsource (lib "eagle-import") (part "R-EU_R1206"))
    )
    (comp (ref "R40")
      (value "47K")
      (footprint "eagle-import:R1206")
      (libsource (lib "eagle-import") (part "R-EU_R1206"))
    )
    (comp (ref "R41")
      (value "13K")
      (footprint "eagle-import:R1206")
      (libsource (lib "eagle-import") (part "R-EU_R1206"))
    )
    (comp (ref "R42")
      (value "1K2")
      (footprint "eagle-import:R1206")
      (libsource (lib "eagle-import") (part "R-EU_R1206"))
    )
    (comp (ref "R43")
      (value "47K")
      (footprint "eagle-import:R1206")
      (libsource (lib "eagle-import") (part "R-EU_R1206"))
    )
    (comp (ref "R44")
      (value "13K")
      (footprint "eagle-import:R1206")
      (libsource (lib "eagle-import") (part "R-EU_R1206"))
    )
    (comp (ref "C24")
      (value "100nF")
      (footprint "eagle-import:WCAP-CSGP_1206_H0.8")
      (libsource (lib "eagle-import") (part "WCAP-CSGP_1206_H0.8_50V(DC)_885012208087"))
    )
    (comp (ref "C25")
      (value "100nF")
      (footprint "eagle-import:WCAP-CSGP_1206_H0.8")
      (libsource (lib "eagle-import") (part "WCAP-CSGP_1206_H0.8_50V(DC)_885012208087"))
    )
    (comp (ref "C26")
      (value "100nF")
      (footprint "eagle-import:WCAP-CSGP_1206_H0.8")
      (libsource (lib "eagle-import") (part "WCAP-CSGP_1206_H0.8_50V(DC)_885012208087"))
    )
    (comp (ref "C27")
      (value "100nF")
      (footprint "eagle-import:WCAP-CSGP_1206_H0.8")
      (libsource (lib "eagle-import") (part "WCAP-CSGP_1206_H0.8_50V(DC)_885012208087"))
    )
    (comp (ref "D12")
      (value "3.3Vdc")
      (footprint "eagle-import:WE-TVS_SOT143-4L")
      (libsource (lib "eagle-import") (part "WE-TVS-HS_SOT143-4L_8240136"))
    )
    (comp (ref "R27")
      (value "1K2")
      (footprint "eagle-import:R1206")
      (libsource (lib "eagle-import") (part "R-EU_R1206"))
    )
    (comp (ref "R28")
      (value "1K2")
      (footprint "eagle-import:R1206")
      (libsource (lib "eagle-import") (part "R-EU_R1206"))
    )
    (comp (ref "R29")
      (value "47K")
      (footprint "eagle-import:R1206")
      (libsource (lib "eagle-import") (part "R-EU_R1206"))
    )
    (comp (ref "R30")
      (value "47K")
      (footprint "eagle-import:R1206")
      (libsource (lib "eagle-import") (part "R-EU_R1206"))
    )
    (comp (ref "R31")
      (value "13K")
      (footprint "eagle-import:R1206")
      (libsource (lib "eagle-import") (part "R-EU_R1206"))
    )
    (comp (ref "R32")
      (value "13K")
      (footprint "eagle-import:R1206")
      (libsource (lib "eagle-import") (part "R-EU_R1206"))
    )
    (comp (ref "C15")
      (value "47nF")
      (footprint "eagle-import:WCAP-CSGP_0805_H0.8_R")
      (libsource (lib "eagle-import") (part "WCAP-CSGP_0805_H0.8_50V(DC)_R_885012207096"))
    )
    (comp (ref "C17")
      (value "100nF")
      (footprint "eagle-import:WCAP-CSGP_0805_H0.8_R")
      (libsource (lib "eagle-import") (part "WCAP-CSGP_0805_H0.8_50V(DC)_R_885012207098"))
    )
    (comp (ref "C19")
      (value "100nF")
      (footprint "eagle-import:WCAP-CSGP_0805_H0.8_R")
      (libsource (lib "eagle-import") (part "WCAP-CSGP_0805_H0.8_50V(DC)_R_885012207098"))
    )
    (comp (ref "D11")
      (value "24Vdc")
      (footprint "eagle-import:WE-TVS_SOT23-3L")
      (libsource (lib "eagle-import") (part "WE-TVS_SOT23-3L_824094024"))
    )
    (comp (ref "R1")
      (value "60R")
      (footprint "eagle-import:R0805")
      (libsource (lib "eagle-import") (part "R-EU_R0805"))
    )
    (comp (ref "R3")
      (value "60R")
      (footprint "eagle-import:R0805")
      (libsource (lib "eagle-import") (part "R-EU_R0805"))
    )
    (comp (ref "U4")
      (value "TLE9250VSJ")
      (footprint "eagle-import:SOIC127P602X173-8N-V")
      (libsource (lib "eagle-import") (part "TLE9250VSJ"))
    )
    (comp (ref "C10")
      (value "22uF")
      (footprint "eagle-import:WCAP-CSGP_1210_H2.5")
      (libsource (lib "eagle-import") (part "WCAP-CSGP_1210_H2.5_25V(DC)_885012109014"))
    )
    (comp (ref "C12")
      (value "22uF")
      (footprint "eagle-import:WCAP-CSGP_0805_H1.25_R")
      (libsource (lib "eagle-import") (part "WCAP-CSGP_0805_H1.25_10V(DC)_885012107011"))
    )
    (comp (ref "C23")
      (value "330 µF")
      (footprint "eagle-import:WCAP-ASLI_12.5X14(DXL)")
      (libsource (lib "eagle-import") (part "WCAP-ASLI_12.5X14_865080662019"))
    )
    (comp (ref "D5")
      (value "33V")
      (footprint "eagle-import:WE-TVSP_DO-214AB_BIDIRECTIONAL")
      (libsource (lib "eagle-import") (part "WE-TVSP_DO-214AB_3000W_BI_824551331"))
    )
    (comp (ref "D006")
      (value "MBRS340T3")
      (footprint "eagle-import:SMC")
      (libsource (lib "eagle-import") (part "MBRS30T34"))
    )
    (comp (ref "G1")
      (value "IFX27001TF_V50")
      (footprint "eagle-import:INF-PG-TO252-3-11_N")
      (libsource (lib "eagle-import") (part "IFX27001TF_V50"))
    )
    (comp (ref "J2")
      (value "645004114822")
      (footprint "eagle-import:645004114822")
      (libsource (lib "eagle-import") (part "645004114822"))
    )
    (comp (ref "J4")
      (value "61300421121")
      (footprint "eagle-import:61300421121")
      (libsource (lib "eagle-import") (part "6130XX21121_61300421121"))
    )
    (comp (ref "C31")
      (value "100nF")
      (footprint "eagle-import:WCAP-CSGP_1206_H0.8")
      (libsource (lib "eagle-import") (part "WCAP-CSGP_1206_H0.8_50V(DC)_885012208087"))
    )
    (comp (ref "C32")
      (value "100nF")
      (footprint "eagle-import:WCAP-CSGP_1206_H0.8")
      (libsource (lib "eagle-import") (part "WCAP-CSGP_1206_H0.8_50V(DC)_885012208087"))
    )
    (comp (ref "C33")
      (value "100nF")
      (footprint "eagle-import:WCAP-CSGP_1206_H0.8")
      (libsource (lib "eagle-import") (part "WCAP-CSGP_1206_H0.8_50V(DC)_885012208087"))
    )
    (comp (ref "C34")
      (value "100nF")
      (footprint "eagle-import:WCAP-CSGP_1206_H0.8")
      (libsource (lib "eagle-import") (part "WCAP-CSGP_1206_H0.8_50V(DC)_885012208087"))
    )
    (comp (ref "D13")
      (value "3.3Vdc")
      (footprint "eagle-import:WE-TVS_SOT143-4L")
      (libsource (lib "eagle-import") (part "WE-TVS-HS_SOT143-4L_8240136"))
    )
    (comp (ref "R21")
      (value "1K2")
      (footprint "eagle-import:R1206")
      (libsource (lib "eagle-import") (part "R-EU_R1206"))
    )
    (comp (ref "R22")
      (value "47K")
      (footprint "eagle-import:R1206")
      (libsource (lib "eagle-import") (part "R-EU_R1206"))
    )
    (comp (ref "R23")
      (value "13K")
      (footprint "eagle-import:R1206")
      (libsource (lib "eagle-import") (part "R-EU_R1206"))
    )
    (comp (ref "R24")
      (value "1K2")
      (footprint "eagle-import:R1206")
      (libsource (lib "eagle-import") (part "R-EU_R1206"))
    )
    (comp (ref "R25")
      (value "47K")
      (footprint "eagle-import:R1206")
      (libsource (lib "eagle-import") (part "R-EU_R1206"))
    )
    (comp (ref "R26")
      (value "13K")
      (footprint "eagle-import:R1206")
      (libsource (lib "eagle-import") (part "R-EU_R1206"))
    )
    (comp (ref "C1")
      (value "100nF")
      (footprint "eagle-import:WCAP-CSGP_0805_H0.8_R")
      (libsource (lib "eagle-import") (part "WCAP-CSGP_0805_H0.8_50V(DC)_R_885012207098"))
    )
    (comp (ref "C13")
      (value "100nF")
      (footprint "eagle-import:WCAP-CSGP_0805_H0.8_R")
      (libsource (lib "eagle-import") (part "WCAP-CSGP_0805_H0.8_50V(DC)_R_885012207098"))
    )
    (comp (ref "C14")
      (value "10nF")
      (footprint "eagle-import:WCAP-CSGP_0805_H0.8_R")
      (libsource (lib "eagle-import") (part "WCAP-CSGP_0805_H0.8_50V(DC)_R_885012207092"))
    )
    (comp (ref "C16")
      (value "10nF")
      (footprint "eagle-import:WCAP-CSGP_0805_H0.8_R")
      (libsource (lib "eagle-import") (part "WCAP-CSGP_0805_H0.8_50V(DC)_R_885012207092"))
    )
    (comp (ref "C18")
      (value "100nF")
      (footprint "eagle-import:WCAP-CSGP_0805_H0.8_R")
      (libsource (lib "eagle-import") (part "WCAP-CSGP_0805_H0.8_50V(DC)_R_885012207098"))
    )
    (comp (ref "C20")
      (value "100nF")
      (footprint "eagle-import:WCAP-CSGP_0805_H0.8_R")
      (libsource (lib "eagle-import") (part "WCAP-CSGP_0805_H0.8_50V(DC)_R_885012207098"))
    )
    (comp (ref "C21")
      (value "10nF")
      (footprint "eagle-import:WCAP-CSGP_0805_H0.8_R")
      (libsource (lib "eagle-import") (part "WCAP-CSGP_0805_H0.8_50V(DC)_R_885012207092"))
    )
    (comp (ref "C22")
      (value "10nF")
      (footprint "eagle-import:WCAP-CSGP_0805_H0.8_R")
      (libsource (lib "eagle-import") (part "WCAP-CSGP_0805_H0.8_50V(DC)_R_885012207092"))
    )
    (comp (ref "D7")
      (value "150141VS73100")
      (footprint "eagle-import:WL-SMTW_3528")
      (libsource (lib "eagle-import") (part "WL-SMTW_3528_150141VS73100"))
    )
    (comp (ref "D8")
      (value "150141VS73100")
      (footprint "eagle-import:WL-SMTW_3528")
      (libsource (lib "eagle-import") (part "WL-SMTW_3528_150141VS73100"))
    )
    (comp (ref "D9")
      (value "150141VS73100")
      (footprint "eagle-import:WL-SMTW_3528")
      (libsource (lib "eagle-import") (part "WL-SMTW_3528_150141VS73100"))
    )
    (comp (ref "D10")
      (value "150141VS73100")
      (footprint "eagle-import:WL-SMTW_3528")
      (libsource (lib "eagle-import") (part "WL-SMTW_3528_150141VS73100"))
    )
    (comp (ref "D020")
      (value "GS1J-L")
      (footprint "eagle-import:SMA_DO-214AC")
      (libsource (lib "eagle-import") (part "GS1-LJ"))
    )
    (comp (ref "D021")
      (value "GS1J-L")
      (footprint "eagle-import:SMA_DO-214AC")
      (libsource (lib "eagle-import") (part "GS1-LJ"))
    )
    (comp (ref "D022")
      (value "GS1J-L")
      (footprint "eagle-import:SMA_DO-214AC")
      (libsource (lib "eagle-import") (part "GS1-LJ"))
    )
    (comp (ref "D023")
      (value "GS1J-L")
      (footprint "eagle-import:SMA_DO-214AC")
      (libsource (lib "eagle-import") (part "GS1-LJ"))
    )
    (comp (ref "R5")
      (value "4k7")
      (footprint "eagle-import:R0805")
      (libsource (lib "eagle-import") (part "R-EU_R0805"))
    )
    (comp (ref "R6")
      (value "4k7")
      (footprint "eagle-import:R0805")
      (libsource (lib "eagle-import") (part "R-EU_R0805"))
    )
    (comp (ref "R8")
      (value "47R")
      (footprint "eagle-import:R0805")
      (libsource (lib "eagle-import") (part "R-EU_R0805"))
    )
    (comp (ref "R9")
      (value "4k7")
      (footprint "eagle-import:R0805")
      (libsource (lib "eagle-import") (part "R-EU_R0805"))
    )
    (comp (ref "R11")
      (value "4k7")
      (footprint "eagle-import:R0805")
      (libsource (lib "eagle-import") (part "R-EU_R0805"))
    )
    (comp (ref "R12")
      (value "47R")
      (footprint "eagle-import:R0805")
      (libsource (lib "eagle-import") (part "R-EU_R0805"))
    )
    (comp (ref "R37")
      (value "1k2")
      (footprint "eagle-import:R0805")
      (libsource (lib "eagle-import") (part "R-EU_R0805"))
    )
    (comp (ref "R38")
      (value "1k2")
      (footprint "eagle-import:R0805")
      (libsource (lib "eagle-import") (part "R-EU_R0805"))
    )
    (comp (ref "RX5")
      (value "470Ohm")
      (footprint "eagle-import:R1206")
      (libsource (lib "eagle-import") (part "R-EU_R1206"))
    )
    (comp (ref "RX6")
      (value "470Ohm")
      (footprint "eagle-import:R1206")
      (libsource (lib "eagle-import") (part "R-EU_R1206"))
    )
    (comp (ref "RX7")
      (value "470Ohm")
      (footprint "eagle-import:R1206")
      (libsource (lib "eagle-import") (part "R-EU_R1206"))
    )
    (comp (ref "RX8")
      (value "470Ohm")
      (footprint "eagle-import:R1206")
      (libsource (lib "eagle-import") (part "R-EU_R1206"))
    )
    (comp (ref "U5")
      (value "BTS7030-2EPA")
      (footprint "eagle-import:SOP65P600X115-15N-V")
      (libsource (lib "eagle-import") (part "BTS7030-2EPA"))
    )
    (comp (ref "U6")
      (value "BTS7030-2EPA")
      (footprint "eagle-import:SOP65P600X115-15N-V")
      (libsource (lib "eagle-import") (part "BTS7030-2EPA"))
    )
    (comp (ref "C2")
      (value "100nF")
      (footprint "eagle-import:WCAP-CSGP_0805_H0.8_R")
      (libsource (lib "eagle-import") (part "WCAP-CSGP_0805_H0.8_50V(DC)_R_885012207098"))
    )
    (comp (ref "C3")
      (value "100nF")
      (footprint "eagle-import:WCAP-CSGP_0805_H0.8_R")
      (libsource (lib "eagle-import") (part "WCAP-CSGP_0805_H0.8_50V(DC)_R_885012207098"))
    )
    (comp (ref "C4")
      (value "10nF")
      (footprint "eagle-import:WCAP-CSGP_0805_H0.8_R")
      (libsource (lib "eagle-import") (part "WCAP-CSGP_0805_H0.8_50V(DC)_R_885012207092"))
    )
    (comp (ref "C5")
      (value "100nF")
      (footprint "eagle-import:WCAP-CSGP_0805_H0.8_R")
      (libsource (lib "eagle-import") (part "WCAP-CSGP_0805_H0.8_50V(DC)_R_885012207098"))
    )
    (comp (ref "C6")
      (value "100nF")
      (footprint "eagle-import:WCAP-CSGP_0805_H0.8_R")
      (libsource (lib "eagle-import") (part "WCAP-CSGP_0805_H0.8_50V(DC)_R_885012207098"))
    )
    (comp (ref "C7")
      (value "10nF")
      (footprint "eagle-import:WCAP-CSGP_0805_H0.8_R")
      (libsource (lib "eagle-import") (part "WCAP-CSGP_0805_H0.8_50V(DC)_R_885012207092"))
    )
    (comp (ref "C8")
      (value "10nF")
      (footprint "eagle-import:WCAP-CSGP_0805_H0.8_R")
      (libsource (lib "eagle-import") (part "WCAP-CSGP_0805_H0.8_50V(DC)_R_885012207092"))
    )
    (comp (ref "C9")
      (value "10nF")
      (footprint "eagle-import:WCAP-CSGP_0805_H0.8_R")
      (libsource (lib "eagle-import") (part "WCAP-CSGP_0805_H0.8_50V(DC)_R_885012207092"))
    )
    (comp (ref "D0")
      (value "33V")
      (footprint "eagle-import:WE-TVSP_DO-214AB_BIDIRECTIONAL")
      (libsource (lib "eagle-import") (part "WE-TVSP_DO-214AB_3000W_BI_824551331"))
    )
    (comp (ref "D1")
      (value "150141VS73100")
      (footprint "eagle-import:WL-SMTW_3528")
      (libsource (lib "eagle-import") (part "WL-SMTW_3528_150141VS73100"))
    )
    (comp (ref "D2")
      (value "150141VS73100")
      (footprint "eagle-import:WL-SMTW_3528")
      (libsource (lib "eagle-import") (part "WL-SMTW_3528_150141VS73100"))
    )
    (comp (ref "D3")
      (value "150141VS73100")
      (footprint "eagle-import:WL-SMTW_3528")
      (libsource (lib "eagle-import") (part "WL-SMTW_3528_150141VS73100"))
    )
    (comp (ref "D4")
      (value "150141VS73100")
      (footprint "eagle-import:WL-SMTW_3528")
      (libsource (lib "eagle-import") (part "WL-SMTW_3528_150141VS73100"))
    )
    (comp (ref "D014")
      (value "GS1J-L")
      (footprint "eagle-import:SMA_DO-214AC")
      (libsource (lib "eagle-import") (part "GS1-LJ"))
    )
    (comp (ref "D016")
      (value "GS1J-L")
      (footprint "eagle-import:SMA_DO-214AC")
      (libsource (lib "eagle-import") (part "GS1-LJ"))
    )
    (comp (ref "D018")
      (value "GS1J-L")
      (footprint "eagle-import:SMA_DO-214AC")
      (libsource (lib "eagle-import") (part "GS1-LJ"))
    )
    (comp (ref "D019")
      (value "GS1J-L")
      (footprint "eagle-import:SMA_DO-214AC")
      (libsource (lib "eagle-import") (part "GS1-LJ"))
    )
    (comp (ref "J5")
      (value "6130XX21121_61300621121")
      (footprint "eagle-import:61300621121")
      (libsource (lib "eagle-import") (part "6130XX21121_61300621121"))
    )
    (comp (ref "J9")
      (value "6130XX21121_61300621121")
      (footprint "eagle-import:61300621121")
      (libsource (lib "eagle-import") (part "6130XX21121_61300621121"))
    )
    (comp (ref "R2")
      (value "4k7")
      (footprint "eagle-import:R0805")
      (libsource (lib "eagle-import") (part "R-EU_R0805"))
    )
    (comp (ref "R4")
      (value "4k7")
      (footprint "eagle-import:R0805")
      (libsource (lib "eagle-import") (part "R-EU_R0805"))
    )
    (comp (ref "R7")
      (value "47R")
      (footprint "eagle-import:R0805")
      (libsource (lib "eagle-import") (part "R-EU_R0805"))
    )
    (comp (ref "R10")
      (value "47R")
      (footprint "eagle-import:R0805")
      (libsource (lib "eagle-import") (part "R-EU_R0805"))
    )
    (comp (ref "R13")
      (value "4k7")
      (footprint "eagle-import:R0805")
      (libsource (lib "eagle-import") (part "R-EU_R0805"))
    )
    (comp (ref "R18")
      (value "4k7")
      (footprint "eagle-import:R0805")
      (libsource (lib "eagle-import") (part "R-EU_R0805"))
    )
    (comp (ref "R35")
      (value "1k2")
      (footprint "eagle-import:R0805")
      (libsource (lib "eagle-import") (part "R-EU_R0805"))
    )
    (comp (ref "R36")
      (value "1k2")
      (footprint "eagle-import:R0805")
      (libsource (lib "eagle-import") (part "R-EU_R0805"))
    )
    (comp (ref "RX1")
      (value "470Ohm")
      (footprint "eagle-import:R1206")
      (libsource (lib "eagle-import") (part "R-EU_R1206"))
    )
    (comp (ref "RX2")
      (value "470Ohm")
      (footprint "eagle-import:R1206")
      (libsource (lib "eagle-import") (part "R-EU_R1206"))
    )
    (comp (ref "RX3")
      (value "470Ohm")
      (footprint "eagle-import:R1206")
      (libsource (lib "eagle-import") (part "R-EU_R1206"))
    )
    (comp (ref "RX4")
      (value "470Ohm")
      (footprint "eagle-import:R1206")
      (libsource (lib "eagle-import") (part "R-EU_R1206"))
    )
    (comp (ref "U2")
      (value "BTS7030-2EPA")
      (footprint "eagle-import:SOP65P600X115-15N-V")
      (libsource (lib "eagle-import") (part "BTS7030-2EPA"))
    )
    (comp (ref "U3")
      (value "BTS7030-2EPA")
      (footprint "eagle-import:SOP65P600X115-15N-V")
      (libsource (lib "eagle-import") (part "BTS7030-2EPA"))
    )
    (comp (ref "ESP32-J1")
      (value "61302211821")
      (footprint "eagle-import:61302211821")
      (libsource (lib "eagle-import") (part "6130XX11821_61302211821"))
    )
    (comp (ref "ESP32-J3")
      (value "61302211821")
      (footprint "eagle-import:61302211821")
      (libsource (lib "eagle-import") (part "6130XX11821_61302211821"))
    )
    (comp (ref "R14")
      (value "13K")
      (footprint "eagle-import:R1206")
      (libsource (lib "eagle-import") (part "R-EU_R1206"))
    )
    (comp (ref "R15")
      (value "13K")
      (footprint "eagle-import:R1206")
      (libsource (lib "eagle-import") (part "R-EU_R1206"))
    )
    (comp (ref "R16")
      (value "13K")
      (footprint "eagle-import:R1206")
      (libsource (lib "eagle-import") (part "R-EU_R1206"))
    )
    (comp (ref "R17")
      (value "13K")
      (footprint "eagle-import:R1206")
      (libsource (lib "eagle-import") (part "R-EU_R1206"))
    )
    (comp (ref "R19")
      (value "13K")
      (footprint "eagle-import:R1206")
      (libsource (lib "eagle-import") (part "R-EU_R1206"))
    )
    (comp (ref "R20")
      (value "13K")
      (footprint "eagle-import:R1206")
      (libsource (lib "eagle-import") (part "R-EU_R1206"))
    )
    (comp (ref "R33")
      (value "13K")
      (footprint "eagle-import:R1206")
      (libsource (lib "eagle-import") (part "R-EU_R1206"))
    )
    (comp (ref "R34")
      (value "13K")
      (footprint "eagle-import:R1206")
      (libsource (lib "eagle-import") (part "R-EU_R1206"))
    )
    (comp (ref "RESET")
      (value "431256083736")
      (footprint "eagle-import:4312560837X6")
      (libsource (lib "eagle-import") (part "431256083736"))
    )
    (comp (ref "C47")
      (value "100nF")
      (footprint "eagle-import:WCAP-CSGP_1206_H0.8")
      (libsource (lib "eagle-import") (part "WCAP-CSGP_1206_H0.8_50V(DC)_885012208087"))
    )
    (comp (ref "C48")
      (value "100nF")
      (footprint "eagle-import:WCAP-CSGP_1206_H0.8")
      (libsource (lib "eagle-import") (part "WCAP-CSGP_1206_H0.8_50V(DC)_885012208087"))
    )
    (comp (ref "C49")
      (value "100nF")
      (footprint "eagle-import:WCAP-CSGP_1206_H0.8")
      (libsource (lib "eagle-import") (part "WCAP-CSGP_1206_H0.8_50V(DC)_885012208087"))
    )
    (comp (ref "C50")
      (value "100nF")
      (footprint "eagle-import:WCAP-CSGP_1206_H0.8")
      (libsource (lib "eagle-import") (part "WCAP-CSGP_1206_H0.8_50V(DC)_885012208087"))
    )
    (comp (ref "D17")
      (value "3.3Vdc")
      (footprint "eagle-import:WE-TVS_SOT143-4L")
      (libsource (lib "eagle-import") (part "WE-TVS-HS_SOT143-4L_8240136"))
    )
    (comp (ref "R51")
      (value "1K2")
      (footprint "eagle-import:R1206")
      (libsource (lib "eagle-import") (part "R-EU_R1206"))
    )
    (comp (ref "R52")
      (value "47K")
      (footprint "eagle-import:R1206")
      (libsource (lib "eagle-import") (part "R-EU_R1206"))
    )
    (comp (ref "R53")
      (value "13K")
      (footprint "eagle-import:R1206")
      (libsource (lib "eagle-import") (part "R-EU_R1206"))
    )
    (comp (ref "R54")
      (value "1K2")
      (footprint "eagle-import:R1206")
      (libsource (lib "eagle-import") (part "R-EU_R1206"))
    )
    (comp (ref "R55")
      (value "47K")
      (footprint "eagle-import:R1206")
      (libsource (lib "eagle-import") (part "R-EU_R1206"))
    )
    (comp (ref "R56")
      (value "13K")
      (footprint "eagle-import:R1206")
      (libsource (lib "eagle-import") (part "R-EU_R1206"))
    )
  )
  (nets
    (net (code "1") (name "+3V3") (class "Default")
      (node (ref "C19") (pin "1") (pinfunction "1_1") (pintype "passive"))
      (node (ref "D12") (pin "4") (pinfunction "VDD_4") (pintype "passive"))
      (node (ref "D13") (pin "4") (pinfunction "VDD_4") (pintype "passive"))
      (node (ref "D15") (pin "4") (pinfunction "VDD_4") (pintype "passive"))
      (node (ref "D17") (pin "4") (pinfunction "VDD_4") (pintype "passive"))
      (node (ref "ESP32-J1") (pin "1") (pinfunction "1_1") (pintype "passive"))
      (node (ref "ESP32-J1") (pin "2") (pinfunction "2_2") (pintype "passive"))
      (node (ref "U4") (pin "5") (pinfunction "VIO_5") (pintype "input"))
    )
    (net (code "2") (name "+5V") (class "Default")
      (node (ref "C12") (pin "2") (pinfunction "2_2") (pintype "passive"))
      (node (ref "C17") (pin "1") (pinfunction "1_1") (pintype "passive"))
      (node (ref "ESP32-J1") (pin "21") (pinfunction "21_21") (pintype "passive"))
      (node (ref "G1") (pin "2") (pinfunction "Q_2") (pintype "power_in"))
      (node (ref "J4") (pin "1") (pinfunction "1_1") (pintype "passive"))
      (node (ref "J4") (pin "2") (pinfunction "2_2") (pintype "passive"))
      (node (ref "J4") (pin "3") (pinfunction "3_3") (pintype "passive"))
      (node (ref "J4") (pin "4") (pinfunction "4_4") (pintype "passive"))
      (node (ref "U4") (pin "3") (pinfunction "VCC_3") (pintype "input"))
    )
    (net (code "3") (name "AGNDU2") (class "Default")
      (node (ref "C6") (pin "2") (pinfunction "2_2") (pintype "passive"))
      (node (ref "R10") (pin "2") (pinfunction "2_2") (pintype "passive"))
      (node (ref "U2") (pin "1") (pinfunction "GND_1") (pintype "power_in"))
    )
    (net (code "4") (name "AGNDU3") (class "Default")
      (node (ref "C3") (pin "2") (pinfunction "2_2") (pintype "passive"))
      (node (ref "R7") (pin "2") (pinfunction "2_2") (pintype "passive"))
      (node (ref "U3") (pin "1") (pinfunction "GND_1") (pintype "power_in"))
    )
    (net (code "5") (name "AGNDU4") (class "Default")
      (node (ref "C13") (pin "2") (pinfunction "2_2") (pintype "passive"))
      (node (ref "R8") (pin "2") (pinfunction "2_2") (pintype "passive"))
      (node (ref "U5") (pin "1") (pinfunction "GND_1") (pintype "power_in"))
    )
    (net (code "6") (name "AGNDU5") (class "Default")
      (node (ref "C20") (pin "2") (pinfunction "2_2") (pintype "passive"))
      (node (ref "R12") (pin "2") (pinfunction "2_2") (pintype "passive"))
      (node (ref "U6") (pin "1") (pinfunction "GND_1") (pintype "power_in"))
    )
    (net (code "7") (name "BOOT") (class "Default")
      (node (ref "ESP32-J3") (pin "14") (pinfunction "14_14") (pintype "passive"))
    )
    (net (code "8") (name "CAN1_RXD") (class "Default")
      (node (ref "ESP32-J1") (pin "5") (pinfunction "5_5") (pintype "passive"))
      (node (ref "U4") (pin "4") (pinfunction "RXD_4") (pintype "output"))
    )
    (net (code "9") (name "CAN1_TXD") (class "Default")
      (node (ref "ESP32-J1") (pin "4") (pinfunction "4_4") (pintype "passive"))
      (node (ref "U4") (pin "1") (pinfunction "TXD_1") (pintype "input"))
    )
    (net (code "10") (name "CAN_N") (class "Default")
      (node (ref "D11") (pin "1") (pinfunction "I/O1_1") (pintype "passive"))
      (node (ref "J2") (pin "1") (pinfunction "1_1") (pintype "passive"))
      (node (ref "R3") (pin "2") (pinfunction "2_2") (pintype "passive"))
      (node (ref "U4") (pin "6") (pinfunction "CANL_6") (pintype "bidirectional"))
    )
    (net (code "11") (name "CAN_P") (class "Default")
      (node (ref "D11") (pin "2") (pinfunction "I/O2_2") (pintype "passive"))
      (node (ref "J2") (pin "2") (pinfunction "2_2") (pintype "passive"))
      (node (ref "R1") (pin "2") (pinfunction "2_2") (pintype "passive"))
      (node (ref "U4") (pin "7") (pinfunction "CANH_7") (pintype "bidirectional"))
    )
    (net (code "12") (name "CI1") (class "Default")
      (node (ref "C32") (pin "1") (pinfunction "1_1") (pintype "passive"))
      (node (ref "D13") (pin "3") (pinfunction "2_3") (pintype "passive"))
      (node (ref "ESP32-J1") (pin "19") (pinfunction "19_19") (pintype "passive"))
      (node (ref "R22") (pin "1") (pinfunction "1_1") (pintype "passive"))
      (node (ref "R23") (pin "2") (pinfunction "2_2") (pintype "passive"))
    )
    (net (code "13") (name "CI2") (class "Default")
      (node (ref "C34") (pin "1") (pinfunction "1_1") (pintype "passive"))
      (node (ref "D13") (pin "2") (pinfunction "1_2") (pintype "passive"))
      (node (ref "ESP32-J1") (pin "18") (pinfunction "18_18") (pintype "passive"))
      (node (ref "R25") (pin "1") (pinfunction "1_1") (pintype "passive"))
      (node (ref "R26") (pin "2") (pinfunction "2_2") (pintype "passive"))
    )
    (net (code "14") (name "CI3") (class "Default")
      (node (ref "C40") (pin "1") (pinfunction "1_1") (pintype "passive"))
      (node (ref "D15") (pin "3") (pinfunction "2_3") (pintype "passive"))
      (node (ref "ESP32-J1") (pin "15") (pinfunction "15_15") (pintype "passive"))
      (node (ref "R40") (pin "1") (pinfunction "1_1") (pintype "passive"))
      (node (ref "R41") (pin "2") (pinfunction "2_2") (pintype "passive"))
    )
    (net (code "15") (name "CI4") (class "Default")
      (node (ref "C42") (pin "1") (pinfunction "1_1") (pintype "passive"))
      (node (ref "D15") (pin "2") (pinfunction "1_2") (pintype "passive"))
      (node (ref "ESP32-J1") (pin "13") (pinfunction "13_13") (pintype "passive"))
      (node (ref "R43") (pin "1") (pinfunction "1_1") (pintype "passive"))
      (node (ref "R44") (pin "2") (pinfunction "2_2") (pintype "passive"))
    )
    (net (code "16") (name "CI5") (class "Default")
      (node (ref "C48") (pin "1") (pinfunction "1_1") (pintype "passive"))
      (node (ref "D17") (pin "3") (pinfunction "2_3") (pintype "passive"))
      (node (ref "ESP32-J1") (pin "11") (pinfunction "11_11") (pintype "passive"))
      (node (ref "R52") (pin "1") (pinfunction "1_1") (pintype "passive"))
      (node (ref "R53") (pin "2") (pinfunction "2_2") (pintype "passive"))
    )
    (net (code "17") (name "CI6") (class "Default")
      (node (ref "C50") (pin "1") (pinfunction "1_1") (pintype "passive"))
      (node (ref "D17") (pin "2") (pinfunction "1_2") (pintype "passive"))
      (node (ref "ESP32-J1") (pin "10") (pinfunction "10_10") (pintype "passive"))
      (node (ref "R55") (pin "1") (pinfunction "1_1") (pintype "passive"))
      (node (ref "R56") (pin "2") (pinfunction "2_2") (pintype "passive"))
    )
    (net (code "18") (name "CI7") (class "Default")
      (node (ref "C27") (pin "1") (pinfunction "1_1") (pintype "passive"))
      (node (ref "D12") (pin "3") (pinfunction "2_3") (pintype "passive"))
      (node (ref "ESP32-J1") (pin "7") (pinfunction "7_7") (pintype "passive"))
      (node (ref "R30") (pin "1") (pinfunction "1_1") (pintype "passive"))
      (node (ref "R32") (pin "2") (pinfunction "2_2") (pintype "passive"))
    )
    (net (code "19") (name "CI8") (class "Default")
      (node (ref "C26") (pin "1") (pinfunction "1_1") (pintype "passive"))
      (node (ref "D12") (pin "2") (pinfunction "1_2") (pintype "passive"))
      (node (ref "ESP32-J1") (pin "6") (pinfunction "6_6") (pintype "passive"))
      (node (ref "R29") (pin "1") (pinfunction "1_1") (pintype "passive"))
      (node (ref "R31") (pin "2") (pinfunction "2_2") (pintype "passive"))
    )
    (net (code "20") (name "ECU_GND") (class "Default")
      (node (ref "C1") (pin "2") (pinfunction "2_2") (pintype "passive"))
      (node (ref "C10") (pin "1") (pinfunction "1_1") (pintype "passive"))
      (node (ref "C12") (pin "1") (pinfunction "1_1") (pintype "passive"))
      (node (ref "C15") (pin "2") (pinfunction "2_2") (pintype "passive"))
      (node (ref "C17") (pin "2") (pinfunction "2_2") (pintype "passive"))
      (node (ref "C18") (pin "2") (pinfunction "2_2") (pintype "passive"))
      (node (ref "C19") (pin "2") (pinfunction "2_2") (pintype "passive"))
      (node (ref "C2") (pin "2") (pinfunction "2_2") (pintype "passive"))
      (node (ref "C23") (pin "2") (pinfunction "-_2") (pintype "passive"))
      (node (ref "C24") (pin "2") (pinfunction "2_2") (pintype "passive"))
      (node (ref "C25") (pin "2") (pinfunction "2_2") (pintype "passive"))
      (node (ref "C26") (pin "2") (pinfunction "2_2") (pintype "passive"))
      (node (ref "C27") (pin "2") (pinfunction "2_2") (pintype "passive"))
      (node (ref "C31") (pin "2") (pinfunction "2_2") (pintype "passive"))
      (node (ref "C32") (pin "2") (pinfunction "2_2") (pintype "passive"))
      (node (ref "C33") (pin "2") (pinfunction "2_2") (pintype "passive"))
      (node (ref "C34") (pin "2") (pinfunction "2_2") (pintype "passive"))
      (node (ref "C39") (pin "2") (pinfunction "2_2") (pintype "passive"))
      (node (ref "C40") (pin "2") (pinfunction "2_2") (pintype "passive"))
      (node (ref "C41") (pin "2") (pinfunction "2_2") (pintype "passive"))
      (node (ref "C42") (pin "2") (pinfunction "2_2") (pintype "passive"))
      (node (ref "C47") (pin "2") (pinfunction "2_2") (pintype "passive"))
      (node (ref "C48") (pin "2") (pinfunction "2_2") (pintype "passive"))
      (node (ref "C49") (pin "2") (pinfunction "2_2") (pintype "passive"))
      (node (ref "C5") (pin "2") (pinfunction "2_2") (pintype "passive"))
      (node (ref "C50") (pin "2") (pinfunction "2_2") (pintype "passive"))
      (node (ref "D11") (pin "3") (pinfunction "GND_3") (pintype "passive"))
      (node (ref "D12") (pin "1") (pinfunction "GND_1") (pintype "passive"))
      (node (ref "D13") (pin "1") (pinfunction "GND_1") (pintype "passive"))
      (node (ref "D15") (pin "1") (pinfunction "GND_1") (pintype "passive"))
      (node (ref "D17") (pin "1") (pinfunction "GND_1") (pintype "passive"))
      (node (ref "D5") (pin "1") (pinfunction "1_1") (pintype "passive"))
      (node (ref "ESP32-J1") (pin "22") (pinfunction "22_22") (pintype "passive"))
      (node (ref "ESP32-J3") (pin "1") (pinfunction "1_1") (pintype "passive"))
      (node (ref "ESP32-J3") (pin "21") (pinfunction "21_21") (pintype "passive"))
      (node (ref "ESP32-J3") (pin "22") (pinfunction "22_22") (pintype "passive"))
      (node (ref "G1") (pin "1") (pinfunction "GND/ADJ_1") (pintype "power_in"))
      (node (ref "J2") (pin "4") (pinfunction "4_4") (pintype "passive"))
      (node (ref "J7") (pin "1") (pinfunction "1_1") (pintype "passive"))
      (node (ref "J7") (pin "2") (pinfunction "2_2") (pintype "passive"))
      (node (ref "J7") (pin "A1") (pinfunction "1_A1") (pintype "passive"))
      (node (ref "J7") (pin "A2") (pinfunction "2_A2") (pintype "passive"))
      (node (ref "J9") (pin "2") (pinfunction "2_2") (pintype "passive"))
      (node (ref "J9") (pin "4") (pinfunction "4_4") (pintype "passive"))
      (node (ref "J9") (pin "6") (pinfunction "6_6") (pintype "passive"))
      (node (ref "R10") (pin "1") (pinfunction "1_1") (pintype "passive"))
      (node (ref "R12") (pin "1") (pinfunction "1_1") (pintype "passive"))
      (node (ref "R14") (pin "1") (pinfunction "1_1") (pintype "passive"))
      (node (ref "R15") (pin "1") (pinfunction "1_1") (pintype "passive"))
      (node (ref "R16") (pin "1") (pinfunction "1_1") (pintype "passive"))
      (node (ref "R17") (pin "1") (pinfunction "1_1") (pintype "passive"))
      (node (ref "R19") (pin "1") (pinfunction "1_1") (pintype "passive"))
      (node (ref "R20") (pin "1") (pinfunction "1_1") (pintype "passive"))
      (node (ref "R21") (pin "1") (pinfunction "1_1") (pintype "passive"))
      (node (ref "R23") (pin "1") (pinfunction "1_1") (pintype "passive"))
      (node (ref "R24") (pin "1") (pinfunction "1_1") (pintype "passive"))
      (node (ref "R26") (pin "1") (pinfunction "1_1") (pintype "passive"))
      (node (ref "R27") (pin "1") (pinfunction "1_1") (pintype "passive"))
      (node (ref "R28") (pin "1") (pinfunction "1_1") (pintype "passive"))
      (node (ref "R31") (pin "1") (pinfunction "1_1") (pintype "passive"))
      (node (ref "R32") (pin "1") (pinfunction "1_1") (pintype "passive"))
      (node (ref "R33") (pin "1") (pinfunction "1_1") (pintype "passive"))
      (node (ref "R34") (pin "1") (pinfunction "1_1") (pintype "passive"))
      (node (ref "R35") (pin "1") (pinfunction "1_1") (pintype "passive"))
      (node (ref "R36") (pin "1") (pinfunction "1_1") (pintype "passive"))
      (node (ref "R37") (pin "1") (pinfunction "1_1") (pintype "passive"))
      (node (ref "R38") (pin "1") (pinfunction "1_1") (pintype "passive"))
      (node (ref "R39") (pin "1") (pinfunction "1_1") (pintype "passive"))
      (node (ref "R41") (pin "1") (pinfunction "1_1") (pintype "passive"))
      (node (ref "R42") (pin "1") (pinfunction "1_1") (pintype "passive"))
      (node (ref "R44") (pin "1") (pinfunction "1_1") (pintype "passive"))
      (node (ref "R51") (pin "1") (pinfunction "1_1") (pintype "passive"))
      (node (ref "R53") (pin "1") (pinfunction "1_1") (pintype "passive"))
      (node (ref "R54") (pin "1") (pinfunction "1_1") (pintype "passive"))
      (node (ref "R56") (pin "1") (pinfunction "1_1") (pintype "passive"))
      (node (ref "R7") (pin "1") (pinfunction "1_1") (pintype "passive"))
      (node (ref "R8") (pin "1") (pinfunction "1_1") (pintype "passive"))
      (node (ref "RESET") (pin "1") (pinfunction "GND1_1") (pintype "passive"))
      (node (ref "RESET") (pin "2") (pinfunction "2_2") (pintype "passive"))
      (node (ref "RESET") (pin "4") (pinfunction "GND_4") (pintype "passive"))
      (node (ref "U4") (pin "2") (pinfunction "GND_2") (pintype "power_in"))
      (node (ref "U4") (pin "8") (pinfunction "NEN_8") (pintype "input"))
    )
    (net (code "21") (name "ECU_PWR") (class "Default")
      (node (ref "D006") (pin "A") (pinfunction "A_A") (pintype "passive"))
      (node (ref "D5") (pin "2") (pinfunction "2_2") (pintype "passive"))
      (node (ref "J2") (pin "3") (pinfunction "3_3") (pintype "passive"))
      (node (ref "J5") (pin "2") (pinfunction "2_2") (pintype "passive"))
      (node (ref "J5") (pin "4") (pinfunction "4_4") (pintype "passive"))
      (node (ref "J5") (pin "6") (pinfunction "6_6") (pintype "passive"))
      (node (ref "J7") (pin "3") (pinfunction "3_3") (pintype "passive"))
      (node (ref "J7") (pin "4") (pinfunction "4_4") (pintype "passive"))
      (node (ref "J7") (pin "A3") (pinfunction "3_A3") (pintype "passive"))
      (node (ref "J7") (pin "A4") (pinfunction "4_A4") (pintype "passive"))
    )
    (net (code "22") (name "I1") (class "Default")
      (node (ref "C31") (pin "1") (pinfunction "1_1") (pintype "passive"))
      (node (ref "J7") (pin "5") (pinfunction "5_5") (pintype "passive"))
      (node (ref "J7") (pin "A5") (pinfunction "5_A5") (pintype "passive"))
      (node (ref "R21") (pin "2") (pinfunction "2_2") (pintype "passive"))
      (node (ref "R22") (pin "2") (pinfunction "2_2") (pintype "passive"))
    )
    (net (code "23") (name "I2") (class "Default")
      (node (ref "C33") (pin "1") (pinfunction "1_1") (pintype "passive"))
      (node (ref "J8") (pin "1") (pinfunction "1_1") (pintype "passive"))
      (node (ref "J8") (pin "A1") (pinfunction "1_A1") (pintype "passive"))
      (node (ref "R24") (pin "2") (pinfunction "2_2") (pintype "passive"))
      (node (ref "R25") (pin "2") (pinfunction "2_2") (pintype "passive"))
    )
    (net (code "24") (name "I3") (class "Default")
      (node (ref "C39") (pin "1") (pinfunction "1_1") (pintype "passive"))
      (node (ref "J8") (pin "2") (pinfunction "2_2") (pintype "passive"))
      (node (ref "J8") (pin "A2") (pinfunction "2_A2") (pintype "passive"))
      (node (ref "R39") (pin "2") (pinfunction "2_2") (pintype "passive"))
      (node (ref "R40") (pin "2") (pinfunction "2_2") (pintype "passive"))
    )
    (net (code "25") (name "I4") (class "Default")
      (node (ref "C41") (pin "1") (pinfunction "1_1") (pintype "passive"))
      (node (ref "J8") (pin "3") (pinfunction "3_3") (pintype "passive"))
      (node (ref "J8") (pin "A3") (pinfunction "3_A3") (pintype "passive"))
      (node (ref "R42") (pin "2") (pinfunction "2_2") (pintype "passive"))
      (node (ref "R43") (pin "2") (pinfunction "2_2") (pintype "passive"))
    )
    (net (code "26") (name "I5") (class "Default")
      (node (ref "C47") (pin "1") (pinfunction "1_1") (pintype "passive"))
      (node (ref "J8") (pin "4") (pinfunction "4_4") (pintype "passive"))
      (node (ref "J8") (pin "A4") (pinfunction "4_A4") (pintype "passive"))
      (node (ref "R51") (pin "2") (pinfunction "2_2") (pintype "passive"))
      (node (ref "R52") (pin "2") (pinfunction "2_2") (pintype "passive"))
    )
    (net (code "27") (name "I6") (class "Default")
      (node (ref "C49") (pin "1") (pinfunction "1_1") (pintype "passive"))
      (node (ref "J8") (pin "5") (pinfunction "5_5") (pintype "passive"))
      (node (ref "J8") (pin "A5") (pinfunction "5_A5") (pintype "passive"))
      (node (ref "R54") (pin "2") (pinfunction "2_2") (pintype "passive"))
      (node (ref "R55") (pin "2") (pinfunction "2_2") (pintype "passive"))
    )
    (net (code "28") (name "I7") (class "Default")
      (node (ref "C25") (pin "1") (pinfunction "1_1") (pintype "passive"))
      (node (ref "J8") (pin "6") (pinfunction "6_6") (pintype "passive"))
      (node (ref "J8") (pin "A6") (pinfunction "6_A6") (pintype "passive"))
      (node (ref "R28") (pin "2") (pinfunction "2_2") (pintype "passive"))
      (node (ref "R30") (pin "2") (pinfunction "2_2") (pintype "passive"))
    )
    (net (code "29") (name "I8") (class "Default")
      (node (ref "C24") (pin "1") (pinfunction "1_1") (pintype "passive"))
      (node (ref "J8") (pin "7") (pinfunction "7_7") (pintype "passive"))
      (node (ref "J8") (pin "A7") (pinfunction "7_A7") (pintype "passive"))
      (node (ref "R27") (pin "2") (pinfunction "2_2") (pintype "passive"))
      (node (ref "R29") (pin "2") (pinfunction "2_2") (pintype "passive"))
    )
    (net (code "30") (name "Net-(C15-Pad1)") (class "Default")
      (node (ref "C15") (pin "1") (pinfunction "1_1") (pintype "passive"))
      (node (ref "R1") (pin "1") (pinfunction "1_1") (pintype "passive"))
      (node (ref "R3") (pin "1") (pinfunction "1_1") (pintype "passive"))
    )
    (net (code "31") (name "Net-(C23-+)") (class "Default")
      (node (ref "C10") (pin "2") (pinfunction "2_2") (pintype "passive"))
      (node (ref "C23") (pin "1") (pinfunction "+_1") (pintype "passive"))
      (node (ref "D006") (pin "C") (pinfunction "C_C") (pintype "passive"))
      (node (ref "G1") (pin "3") (pinfunction "I_3") (pintype "power_in"))
    )
    (net (code "32") (name "Net-(D1--)") (class "Default")
      (node (ref "D1") (pin "1") (pinfunction "-_1") (pintype "passive"))
      (node (ref "RX1") (pin "2") (pinfunction "2_2") (pintype "passive"))
    )
    (net (code "33") (name "Net-(D2--)") (class "Default")
      (node (ref "D2") (pin "1") (pinfunction "-_1") (pintype "passive"))
      (node (ref "RX2") (pin "1") (pinfunction "1_1") (pintype "passive"))
    )
    (net (code "34") (name "Net-(D3--)") (class "Default")
      (node (ref "D3") (pin "1") (pinfunction "-_1") (pintype "passive"))
      (node (ref "RX3") (pin "2") (pinfunction "2_2") (pintype "passive"))
    )
    (net (code "35") (name "Net-(D4--)") (class "Default")
      (node (ref "D4") (pin "1") (pinfunction "-_1") (pintype "passive"))
      (node (ref "RX4") (pin "1") (pinfunction "1_1") (pintype "passive"))
    )
    (net (code "36") (name "Net-(D7--)") (class "Default")
      (node (ref "D7") (pin "1") (pinfunction "-_1") (pintype "passive"))
      (node (ref "RX6") (pin "1") (pinfunction "1_1") (pintype "passive"))
    )
    (net (code "37") (name "Net-(D8--)") (class "Default")
      (node (ref "D8") (pin "1") (pinfunction "-_1") (pintype "passive"))
      (node (ref "RX7") (pin "2") (pinfunction "2_2") (pintype "passive"))
    )
    (net (code "38") (name "Net-(D9--)") (class "Default")
      (node (ref "D9") (pin "1") (pinfunction "-_1") (pintype "passive"))
      (node (ref "RX5") (pin "1") (pinfunction "1_1") (pintype "passive"))
    )
    (net (code "39") (name "Net-(D10--)") (class "Default")
      (node (ref "D10") (pin "1") (pinfunction "-_1") (pintype "passive"))
      (node (ref "RX8") (pin "2") (pinfunction "2_2") (pintype "passive"))
    )
    (net (code "40") (name "Net-(U2-IN0)") (class "Default")
      (node (ref "R18") (pin "2") (pinfunction "2_2") (pintype "passive"))
      (node (ref "U2") (pin "2") (pinfunction "IN0_2") (pintype "input"))
    )
    (net (code "41") (name "Net-(U2-IN1)") (class "Default")
      (node (ref "R13") (pin "2") (pinfunction "2_2") (pintype "passive"))
      (node (ref "U2") (pin "6") (pinfunction "IN1_6") (pintype "input"))
    )
    (net (code "42") (name "Net-(U3-IN0)") (class "Default")
      (node (ref "R2") (pin "2") (pinfunction "2_2") (pintype "passive"))
      (node (ref "U3") (pin "2") (pinfunction "IN0_2") (pintype "input"))
    )
    (net (code "43") (name "Net-(U3-IN1)") (class "Default")
      (node (ref "R4") (pin "2") (pinfunction "2_2") (pintype "passive"))
      (node (ref "U3") (pin "6") (pinfunction "IN1_6") (pintype "input"))
    )
    (net (code "44") (name "Net-(U5-IN0)") (class "Default")
      (node (ref "R5") (pin "2") (pinfunction "2_2") (pintype "passive"))
      (node (ref "U5") (pin "2") (pinfunction "IN0_2") (pintype "input"))
    )
    (net (code "45") (name "Net-(U5-IN1)") (class "Default")
      (node (ref "R6") (pin "2") (pinfunction "2_2") (pintype "passive"))
      (node (ref "U5") (pin "6") (pinfunction "IN1_6") (pintype "input"))
    )
    (net (code "46") (name "Net-(U6-IN0)") (class "Default")
      (node (ref "R9") (pin "2") (pinfunction "2_2") (pintype "passive"))
      (node (ref "U6") (pin "2") (pinfunction "IN0_2") (pintype "input"))
    )
    (net (code "47") (name "Net-(U6-IN1)") (class "Default")
      (node (ref "R11") (pin "2") (pinfunction "2_2") (pintype "passive"))
      (node (ref "U6") (pin "6") (pinfunction "IN1_6") (pintype "input"))
    )
    (net (code "48") (name "PWR") (class "Default")
      (node (ref "C1") (pin "1") (pinfunction "1_1") (pintype "passive"))
      (node (ref "C13") (pin "1") (pinfunction "1_1") (pintype "passive"))
      (node (ref "C18") (pin "1") (pinfunction "1_1") (pintype "passive"))
      (node (ref "C2") (pin "1") (pinfunction "1_1") (pintype "passive"))
      (node (ref "C20") (pin "1") (pinfunction "1_1") (pintype "passive"))
      (node (ref "C3") (pin "1") (pinfunction "1_1") (pintype "passive"))
      (node (ref "C5") (pin "1") (pinfunction "1_1") (pintype "passive"))
      (node (ref "C6") (pin "1") (pinfunction "1_1") (pintype "passive"))
      (node (ref "D0") (pin "2") (pinfunction "2_2") (pintype "passive"))
      (node (ref "J13") (pin "4") (pinfunction "4_4") (pintype "passive"))
      (node (ref "J13") (pin "A4") (pinfunction "4_A4") (pintype "passive"))
      (node (ref "J5") (pin "1") (pinfunction "1_1") (pintype "passive"))
      (node (ref "J5") (pin "3") (pinfunction "3_3") (pintype "passive"))
      (node (ref "J5") (pin "5") (pinfunction "5_5") (pintype "passive"))
      (node (ref "U2") (pin "15") (pinfunction "VS_15") (pintype "power_in"))
      (node (ref "U3") (pin "15") (pinfunction "VS_15") (pintype "power_in"))
      (node (ref "U5") (pin "15") (pinfunction "VS_15") (pintype "power_in"))
      (node (ref "U6") (pin "15") (pinfunction "VS_15") (pintype "power_in"))
    )
    (net (code "49") (name "PWR_GND") (class "Default")
      (node (ref "C14") (pin "1") (pinfunction "1_1") (pintype "passive"))
      (node (ref "C16") (pin "2") (pinfunction "2_2") (pintype "passive"))
      (node (ref "C21") (pin "1") (pinfunction "1_1") (pintype "passive"))
      (node (ref "C22") (pin "2") (pinfunction "2_2") (pintype "passive"))
      (node (ref "C4") (pin "1") (pinfunction "1_1") (pintype "passive"))
      (node (ref "C7") (pin "1") (pinfunction "1_1") (pintype "passive"))
      (node (ref "C8") (pin "2") (pinfunction "2_2") (pintype "passive"))
      (node (ref "C9") (pin "2") (pinfunction "2_2") (pintype "passive"))
      (node (ref "D0") (pin "1") (pinfunction "1_1") (pintype "passive"))
      (node (ref "D014") (pin "A") (pinfunction "A_A") (pintype "passive"))
      (node (ref "D016") (pin "A") (pinfunction "A_A") (pintype "passive"))
      (node (ref "D018") (pin "A") (pinfunction "A_A") (pintype "passive"))
      (node (ref "D019") (pin "A") (pinfunction "A_A") (pintype "passive"))
      (node (ref "D020") (pin "A") (pinfunction "A_A") (pintype "passive"))
      (node (ref "D021") (pin "A") (pinfunction "A_A") (pintype "passive"))
      (node (ref "D022") (pin "A") (pinfunction "A_A") (pintype "passive"))
      (node (ref "D023") (pin "A") (pinfunction "A_A") (pintype "passive"))
      (node (ref "J1") (pin "1") (pinfunction "1_1") (pintype "passive"))
      (node (ref "J1") (pin "4") (pinfunction "4_4") (pintype "passive"))
      (node (ref "J1") (pin "5") (pinfunction "5_5") (pintype "passive"))
      (node (ref "J1") (pin "A1") (pinfunction "1_A1") (pintype "passive"))
      (node (ref "J1") (pin "A4") (pinfunction "4_A4") (pintype "passive"))
      (node (ref "J1") (pin "A5") (pinfunction "5_A5") (pintype "passive"))
      (node (ref "J13") (pin "3") (pinfunction "3_3") (pintype "passive"))
      (node (ref "J13") (pin "5") (pinfunction "5_5") (pintype "passive"))
      (node (ref "J13") (pin "A3") (pinfunction "3_A3") (pintype "passive"))
      (node (ref "J13") (pin "A5") (pinfunction "5_A5") (pintype "passive"))
      (node (ref "J15") (pin "3") (pinfunction "3_3") (pintype "passive"))
      (node (ref "J15") (pin "4") (pinfunction "4_4") (pintype "passive"))
      (node (ref "J15") (pin "7") (pinfunction "7_7") (pintype "passive"))
      (node (ref "J15") (pin "8") (pinfunction "8_8") (pintype "passive"))
      (node (ref "J15") (pin "A3") (pinfunction "3_A3") (pintype "passive"))
      (node (ref "J15") (pin "A4") (pinfunction "4_A4") (pintype "passive"))
      (node (ref "J15") (pin "A7") (pinfunction "7_A7") (pintype "passive"))
      (node (ref "J15") (pin "A8") (pinfunction "8_A8") (pintype "passive"))
      (node (ref "J9") (pin "1") (pinfunction "1_1") (pintype "passive"))
      (node (ref "J9") (pin "3") (pinfunction "3_3") (pintype "passive"))
      (node (ref "J9") (pin "5") (pinfunction "5_5") (pintype "passive"))
      (node (ref "RX1") (pin "1") (pinfunction "1_1") (pintype "passive"))
      (node (ref "RX2") (pin "2") (pinfunction "2_2") (pintype "passive"))
      (node (ref "RX3") (pin "1") (pinfunction "1_1") (pintype "passive"))
      (node (ref "RX4") (pin "2") (pinfunction "2_2") (pintype "passive"))
      (node (ref "RX5") (pin "2") (pinfunction "2_2") (pintype "passive"))
      (node (ref "RX6") (pin "2") (pinfunction "2_2") (pintype "passive"))
      (node (ref "RX7") (pin "1") (pinfunction "1_1") (pintype "passive"))
      (node (ref "RX8") (pin "1") (pinfunction "1_1") (pintype "passive"))
    )
    (net (code "50") (name "Q1") (class "Default")
      (node (ref "C7") (pin "2") (pinfunction "2_2") (pintype "passive"))
      (node (ref "D014") (pin "C") (pinfunction "C_C") (pintype "passive"))
      (node (ref "D1") (pin "2") (pinfunction "+_2") (pintype "passive"))
      (node (ref "J13") (pin "2") (pinfunction "2_2") (pintype "passive"))
      (node (ref "J13") (pin "A2") (pinfunction "2_A2") (pintype "passive"))
      (node (ref "U2") (pin "10") (pinfunction "OUT1C_10") (pintype "output"))
      (node (ref "U2") (pin "8") (pinfunction "OUT1A_8") (pintype "output"))
      (node (ref "U2") (pin "9") (pinfunction "OUT1B_9") (pintype "output"))
    )
    (net (code "51") (name "Q1C") (class "Default")
      (node (ref "ESP32-J3") (pin "18") (pinfunction "18_18") (pintype "passive"))
      (node (ref "R13") (pin "1") (pinfunction "1_1") (pintype "passive"))
      (node (ref "R33") (pin "2") (pinfunction "2_2") (pintype "passive"))
    )
    (net (code "52") (name "Q2") (class "Default")
      (node (ref "C8") (pin "1") (pinfunction "1_1") (pintype "passive"))
      (node (ref "D019") (pin "C") (pinfunction "C_C") (pintype "passive"))
      (node (ref "D2") (pin "2") (pinfunction "+_2") (pintype "passive"))
      (node (ref "J13") (pin "1") (pinfunction "1_1") (pintype "passive"))
      (node (ref "J13") (pin "A1") (pinfunction "1_A1") (pintype "passive"))
      (node (ref "U2") (pin "12") (pinfunction "OUT0A_12") (pintype "output"))
      (node (ref "U2") (pin "13") (pinfunction "OUT0B_13") (pintype "output"))
      (node (ref "U2") (pin "14") (pinfunction "OUT0C_14") (pintype "output"))
    )
    (net (code "53") (name "Q2C") (class "Default")
      (node (ref "ESP32-J3") (pin "17") (pinfunction "17_17") (pintype "passive"))
      (node (ref "R15") (pin "2") (pinfunction "2_2") (pintype "passive"))
      (node (ref "R18") (pin "1") (pinfunction "1_1") (pintype "passive"))
    )
    (net (code "54") (name "Q3") (class "Default")
      (node (ref "C4") (pin "2") (pinfunction "2_2") (pintype "passive"))
      (node (ref "D016") (pin "C") (pinfunction "C_C") (pintype "passive"))
      (node (ref "D3") (pin "2") (pinfunction "+_2") (pintype "passive"))
      (node (ref "J15") (pin "6") (pinfunction "6_6") (pintype "passive"))
      (node (ref "J15") (pin "A6") (pinfunction "6_A6") (pintype "passive"))
      (node (ref "U3") (pin "10") (pinfunction "OUT1C_10") (pintype "output"))
      (node (ref "U3") (pin "8") (pinfunction "OUT1A_8") (pintype "output"))
      (node (ref "U3") (pin "9") (pinfunction "OUT1B_9") (pintype "output"))
    )
    (net (code "55") (name "Q3C") (class "Default")
      (node (ref "ESP32-J3") (pin "9") (pinfunction "9_9") (pintype "passive"))
      (node (ref "R14") (pin "2") (pinfunction "2_2") (pintype "passive"))
      (node (ref "R4") (pin "1") (pinfunction "1_1") (pintype "passive"))
    )
    (net (code "56") (name "Q4") (class "Default")
      (node (ref "C9") (pin "1") (pinfunction "1_1") (pintype "passive"))
      (node (ref "D018") (pin "C") (pinfunction "C_C") (pintype "passive"))
      (node (ref "D4") (pin "2") (pinfunction "+_2") (pintype "passive"))
      (node (ref "J15") (pin "5") (pinfunction "5_5") (pintype "passive"))
      (node (ref "J15") (pin "A5") (pinfunction "5_A5") (pintype "passive"))
      (node (ref "U3") (pin "12") (pinfunction "OUT0A_12") (pintype "output"))
      (node (ref "U3") (pin "13") (pinfunction "OUT0B_13") (pintype "output"))
      (node (ref "U3") (pin "14") (pinfunction "OUT0C_14") (pintype "output"))
    )
    (net (code "57") (name "Q4C") (class "Default")
      (node (ref "ESP32-J3") (pin "8") (pinfunction "8_8") (pintype "passive"))
      (node (ref "R16") (pin "2") (pinfunction "2_2") (pintype "passive"))
      (node (ref "R2") (pin "1") (pinfunction "1_1") (pintype "passive"))
    )
    (net (code "58") (name "Q5") (class "Default")
      (node (ref "C14") (pin "2") (pinfunction "2_2") (pintype "passive"))
      (node (ref "D020") (pin "C") (pinfunction "C_C") (pintype "passive"))
      (node (ref "D8") (pin "2") (pinfunction "+_2") (pintype "passive"))
      (node (ref "J15") (pin "2") (pinfunction "2_2") (pintype "passive"))
      (node (ref "J15") (pin "A2") (pinfunction "2_A2") (pintype "passive"))
      (node (ref "U5") (pin "10") (pinfunction "OUT1C_10") (pintype "output"))
      (node (ref "U5") (pin "8") (pinfunction "OUT1A_8") (pintype "output"))
      (node (ref "U5") (pin "9") (pinfunction "OUT1B_9") (pintype "output"))
    )
    (net (code "59") (name "Q5C") (class "Default")
      (node (ref "ESP32-J3") (pin "7") (pinfunction "7_7") (pintype "passive"))
      (node (ref "R17") (pin "2") (pinfunction "2_2") (pintype "passive"))
      (node (ref "R6") (pin "1") (pinfunction "1_1") (pintype "passive"))
    )
    (net (code "60") (name "Q6") (class "Default")
      (node (ref "C16") (pin "1") (pinfunction "1_1") (pintype "passive"))
      (node (ref "D021") (pin "C") (pinfunction "C_C") (pintype "passive"))
      (node (ref "D7") (pin "2") (pinfunction "+_2") (pintype "passive"))
      (node (ref "J15") (pin "1") (pinfunction "1_1") (pintype "passive"))
      (node (ref "J15") (pin "A1") (pinfunction "1_A1") (pintype "passive"))
      (node (ref "U5") (pin "12") (pinfunction "OUT0A_12") (pintype "output"))
      (node (ref "U5") (pin "13") (pinfunction "OUT0B_13") (pintype "output"))
      (node (ref "U5") (pin "14") (pinfunction "OUT0C_14") (pintype "output"))
    )
    (net (code "61") (name "Q6C") (class "Default")
      (node (ref "ESP32-J3") (pin "6") (pinfunction "6_6") (pintype "passive"))
      (node (ref "R19") (pin "2") (pinfunction "2_2") (pintype "passive"))
      (node (ref "R5") (pin "1") (pinfunction "1_1") (pintype "passive"))
    )
    (net (code "62") (name "Q7") (class "Default")
      (node (ref "C21") (pin "2") (pinfunction "2_2") (pintype "passive"))
      (node (ref "D022") (pin "C") (pinfunction "C_C") (pintype "passive"))
      (node (ref "D10") (pin "2") (pinfunction "+_2") (pintype "passive"))
      (node (ref "J1") (pin "3") (pinfunction "3_3") (pintype "passive"))
      (node (ref "J1") (pin "A3") (pinfunction "3_A3") (pintype "passive"))
      (node (ref "U6") (pin "10") (pinfunction "OUT1C_10") (pintype "output"))
      (node (ref "U6") (pin "8") (pinfunction "OUT1A_8") (pintype "output"))
      (node (ref "U6") (pin "9") (pinfunction "OUT1B_9") (pintype "output"))
    )
    (net (code "63") (name "Q7C") (class "Default")
      (node (ref "ESP32-J3") (pin "4") (pinfunction "4_4") (pintype "passive"))
      (node (ref "R11") (pin "1") (pinfunction "1_1") (pintype "passive"))
      (node (ref "R20") (pin "2") (pinfunction "2_2") (pintype "passive"))
    )
    (net (code "64") (name "Q8") (class "Default")
      (node (ref "C22") (pin "1") (pinfunction "1_1") (pintype "passive"))
      (node (ref "D023") (pin "C") (pinfunction "C_C") (pintype "passive"))
      (node (ref "D9") (pin "2") (pinfunction "+_2") (pintype "passive"))
      (node (ref "J1") (pin "2") (pinfunction "2_2") (pintype "passive"))
      (node (ref "J1") (pin "A2") (pinfunction "2_A2") (pintype "passive"))
      (node (ref "U6") (pin "12") (pinfunction "OUT0A_12") (pintype "output"))
      (node (ref "U6") (pin "13") (pinfunction "OUT0B_13") (pintype "output"))
      (node (ref "U6") (pin "14") (pinfunction "OUT0C_14") (pintype "output"))
    )
    (net (code "65") (name "Q8C") (class "Default")
      (node (ref "ESP32-J3") (pin "5") (pinfunction "5_5") (pintype "passive"))
      (node (ref "R34") (pin "2") (pinfunction "2_2") (pintype "passive"))
      (node (ref "R9") (pin "1") (pinfunction "1_1") (pintype "passive"))
    )
    (net (code "66") (name "RESET") (class "Default")
      (node (ref "ESP32-J1") (pin "3") (pinfunction "3_3") (pintype "passive"))
      (node (ref "RESET") (pin "3") (pinfunction "3_3") (pintype "passive"))
    )
    (net (code "67") (name "U2IS") (class "Default")
      (node (ref "R35") (pin "2") (pinfunction "2_2") (pintype "passive"))
      (node (ref "U2") (pin "4") (pinfunction "IS_4") (pintype "output"))
    )
    (net (code "68") (name "U3IS") (class "Default")
      (node (ref "R36") (pin "2") (pinfunction "2_2") (pintype "passive"))
      (node (ref "U3") (pin "4") (pinfunction "IS_4") (pintype "output"))
    )
    (net (code "69") (name "U5IS") (class "Default")
      (node (ref "R37") (pin "2") (pinfunction "2_2") (pintype "passive"))
      (node (ref "U5") (pin "4") (pinfunction "IS_4") (pintype "output"))
    )
    (net (code "70") (name "U6IS") (class "Default")
      (node (ref "R38") (pin "2") (pinfunction "2_2") (pintype "passive"))
      (node (ref "U6") (pin "4") (pinfunction "IS_4") (pintype "output"))
    )
    (net (code "71") (name "unconnected-(ESP32-J1-Pad8)") (class "Default")
      (node (ref "ESP32-J1") (pin "8") (pinfunction "8_8") (pintype "passive"))
    )
    (net (code "72") (name "unconnected-(ESP32-J1-Pad9)") (class "Default")
      (node (ref "ESP32-J1") (pin "9") (pinfunction "9_9") (pintype "passive"))
    )
    (net (code "73") (name "unconnected-(ESP32-J1-Pad12)") (class "Default")
      (node (ref "ESP32-J1") (pin "12") (pinfunction "12_12") (pintype "passive"))
    )
    (net (code "74") (name "unconnected-(ESP32-J1-Pad14)") (class "Default")
      (node (ref "ESP32-J1") (pin "14") (pinfunction "14_14") (pintype "passive"))
    )
    (net (code "75") (name "unconnected-(ESP32-J1-Pad16)") (class "Default")
      (node (ref "ESP32-J1") (pin "16") (pinfunction "16_16") (pintype "passive"))
    )
    (net (code "76") (name "unconnected-(ESP32-J1-Pad17)") (class "Default")
      (node (ref "ESP32-J1") (pin "17") (pinfunction "17_17") (pintype "passive"))
    )
    (net (code "77") (name "unconnected-(ESP32-J1-Pad20)") (class "Default")
      (node (ref "ESP32-J1") (pin "20") (pinfunction "20_20") (pintype "passive"))
    )
    (net (code "78") (name "unconnected-(ESP32-J3-Pad2)") (class "Default")
      (node (ref "ESP32-J3") (pin "2") (pinfunction "2_2") (pintype "passive"))
    )
    (net (code "79") (name "unconnected-(ESP32-J3-Pad3)") (class "Default")
      (node (ref "ESP32-J3") (pin "3") (pinfunction "3_3") (pintype "passive"))
    )
    (net (code "80") (name "unconnected-(ESP32-J3-Pad10)") (class "Default")
      (node (ref "ESP32-J3") (pin "10") (pinfunction "10_10") (pintype "passive"))
    )
    (net (code "81") (name "unconnected-(ESP32-J3-Pad11)") (class "Default")
      (node (ref "ESP32-J3") (pin "11") (pinfunction "11_11") (pintype "passive"))
    )
    (net (code "82") (name "unconnected-(ESP32-J3-Pad12)") (class "Default")
      (node (ref "ESP32-J3") (pin "12") (pinfunction "12_12") (pintype "passive"))
    )
    (net (code "83") (name "unconnected-(ESP32-J3-Pad13)") (class "Default")
      (node (ref "ESP32-J3") (pin "13") (pinfunction "13_13") (pintype "passive"))
    )
    (net (code "84") (name "unconnected-(ESP32-J3-Pad15)") (class "Default")
      (node (ref "ESP32-J3") (pin "15") (pinfunction "15_15") (pintype "passive"))
    )
    (net (code "85") (name "unconnected-(ESP32-J3-Pad16)") (class "Default")
      (node (ref "ESP32-J3") (pin "16") (pinfunction "16_16") (pintype "passive"))
    )
    (net (code "86") (name "unconnected-(ESP32-J3-Pad19)") (class "Default")
      (node (ref "ESP32-J3") (pin "19") (pinfunction "19_19") (pintype "passive"))
    )
    (net (code "87") (name "unconnected-(ESP32-J3-Pad20)") (class "Default")
      (node (ref "ESP32-J3") (pin "20") (pinfunction "20_20") (pintype "passive"))
    )
    (net (code "88") (name "unconnected-(U2-DEN-Pad3)") (class "Default")
      (node (ref "U2") (pin "3") (pinfunction "DEN_3") (pintype "input"))
    )
    (net (code "89") (name "unconnected-(U2-DSEL-Pad5)") (class "Default")
      (node (ref "U2") (pin "5") (pinfunction "DSEL_5") (pintype "input"))
    )
    (net (code "90") (name "unconnected-(U2-NC1-Pad7)") (class "Default")
      (node (ref "U2") (pin "7") (pinfunction "NC1_7") (pintype "passive"))
    )
    (net (code "91") (name "unconnected-(U2-NC2-Pad11)") (class "Default")
      (node (ref "U2") (pin "11") (pinfunction "NC2_11") (pintype "passive"))
    )
    (net (code "92") (name "unconnected-(U3-DEN-Pad3)") (class "Default")
      (node (ref "U3") (pin "3") (pinfunction "DEN_3") (pintype "input"))
    )
    (net (code "93") (name "unconnected-(U3-DSEL-Pad5)") (class "Default")
      (node (ref "U3") (pin "5") (pinfunction "DSEL_5") (pintype "input"))
    )
    (net (code "94") (name "unconnected-(U3-NC1-Pad7)") (class "Default")
      (node (ref "U3") (pin "7") (pinfunction "NC1_7") (pintype "passive"))
    )
    (net (code "95") (name "unconnected-(U3-NC2-Pad11)") (class "Default")
      (node (ref "U3") (pin "11") (pinfunction "NC2_11") (pintype "passive"))
    )
    (net (code "96") (name "unconnected-(U5-DEN-Pad3)") (class "Default")
      (node (ref "U5") (pin "3") (pinfunction "DEN_3") (pintype "input"))
    )
    (net (code "97") (name "unconnected-(U5-DSEL-Pad5)") (class "Default")
      (node (ref "U5") (pin "5") (pinfunction "DSEL_5") (pintype "input"))
    )
    (net (code "98") (name "unconnected-(U5-NC1-Pad7)") (class "Default")
      (node (ref "U5") (pin "7") (pinfunction "NC1_7") (pintype "passive"))
    )
    (net (code "99") (name "unconnected-(U5-NC2-Pad11)") (class "Default")
      (node (ref "U5") (pin "11") (pinfunction "NC2_11") (pintype "passive"))
    )
    (net (code "100") (name "unconnected-(U6-DEN-Pad3)") (class "Default")
      (node (ref "U6") (pin "3") (pinfunction "DEN_3") (pintype "input"))
    )
    (net (code "101") (name "unconnected-(U6-DSEL-Pad5)") (class "Default")
      (node (ref "U6") (pin "5") (pinfunction "DSEL_5") (pintype "input"))
    )
    (net (code "102") (name "unconnected-(U6-NC1-Pad7)") (class "Default")
      (node (ref "U6") (pin "7") (pinfunction "NC1_7") (pintype "passive"))
    )
    (net (code "103") (name "unconnected-(U6-NC2-Pad11)") (class "Default")
      (node (ref "U6") (pin "11") (pinfunction "NC2_11") (pintype "passive"))
    )
  )
)
